# Ringo3-Eagle6.net
KiCad netlist of a schematic drawn in EAGLE
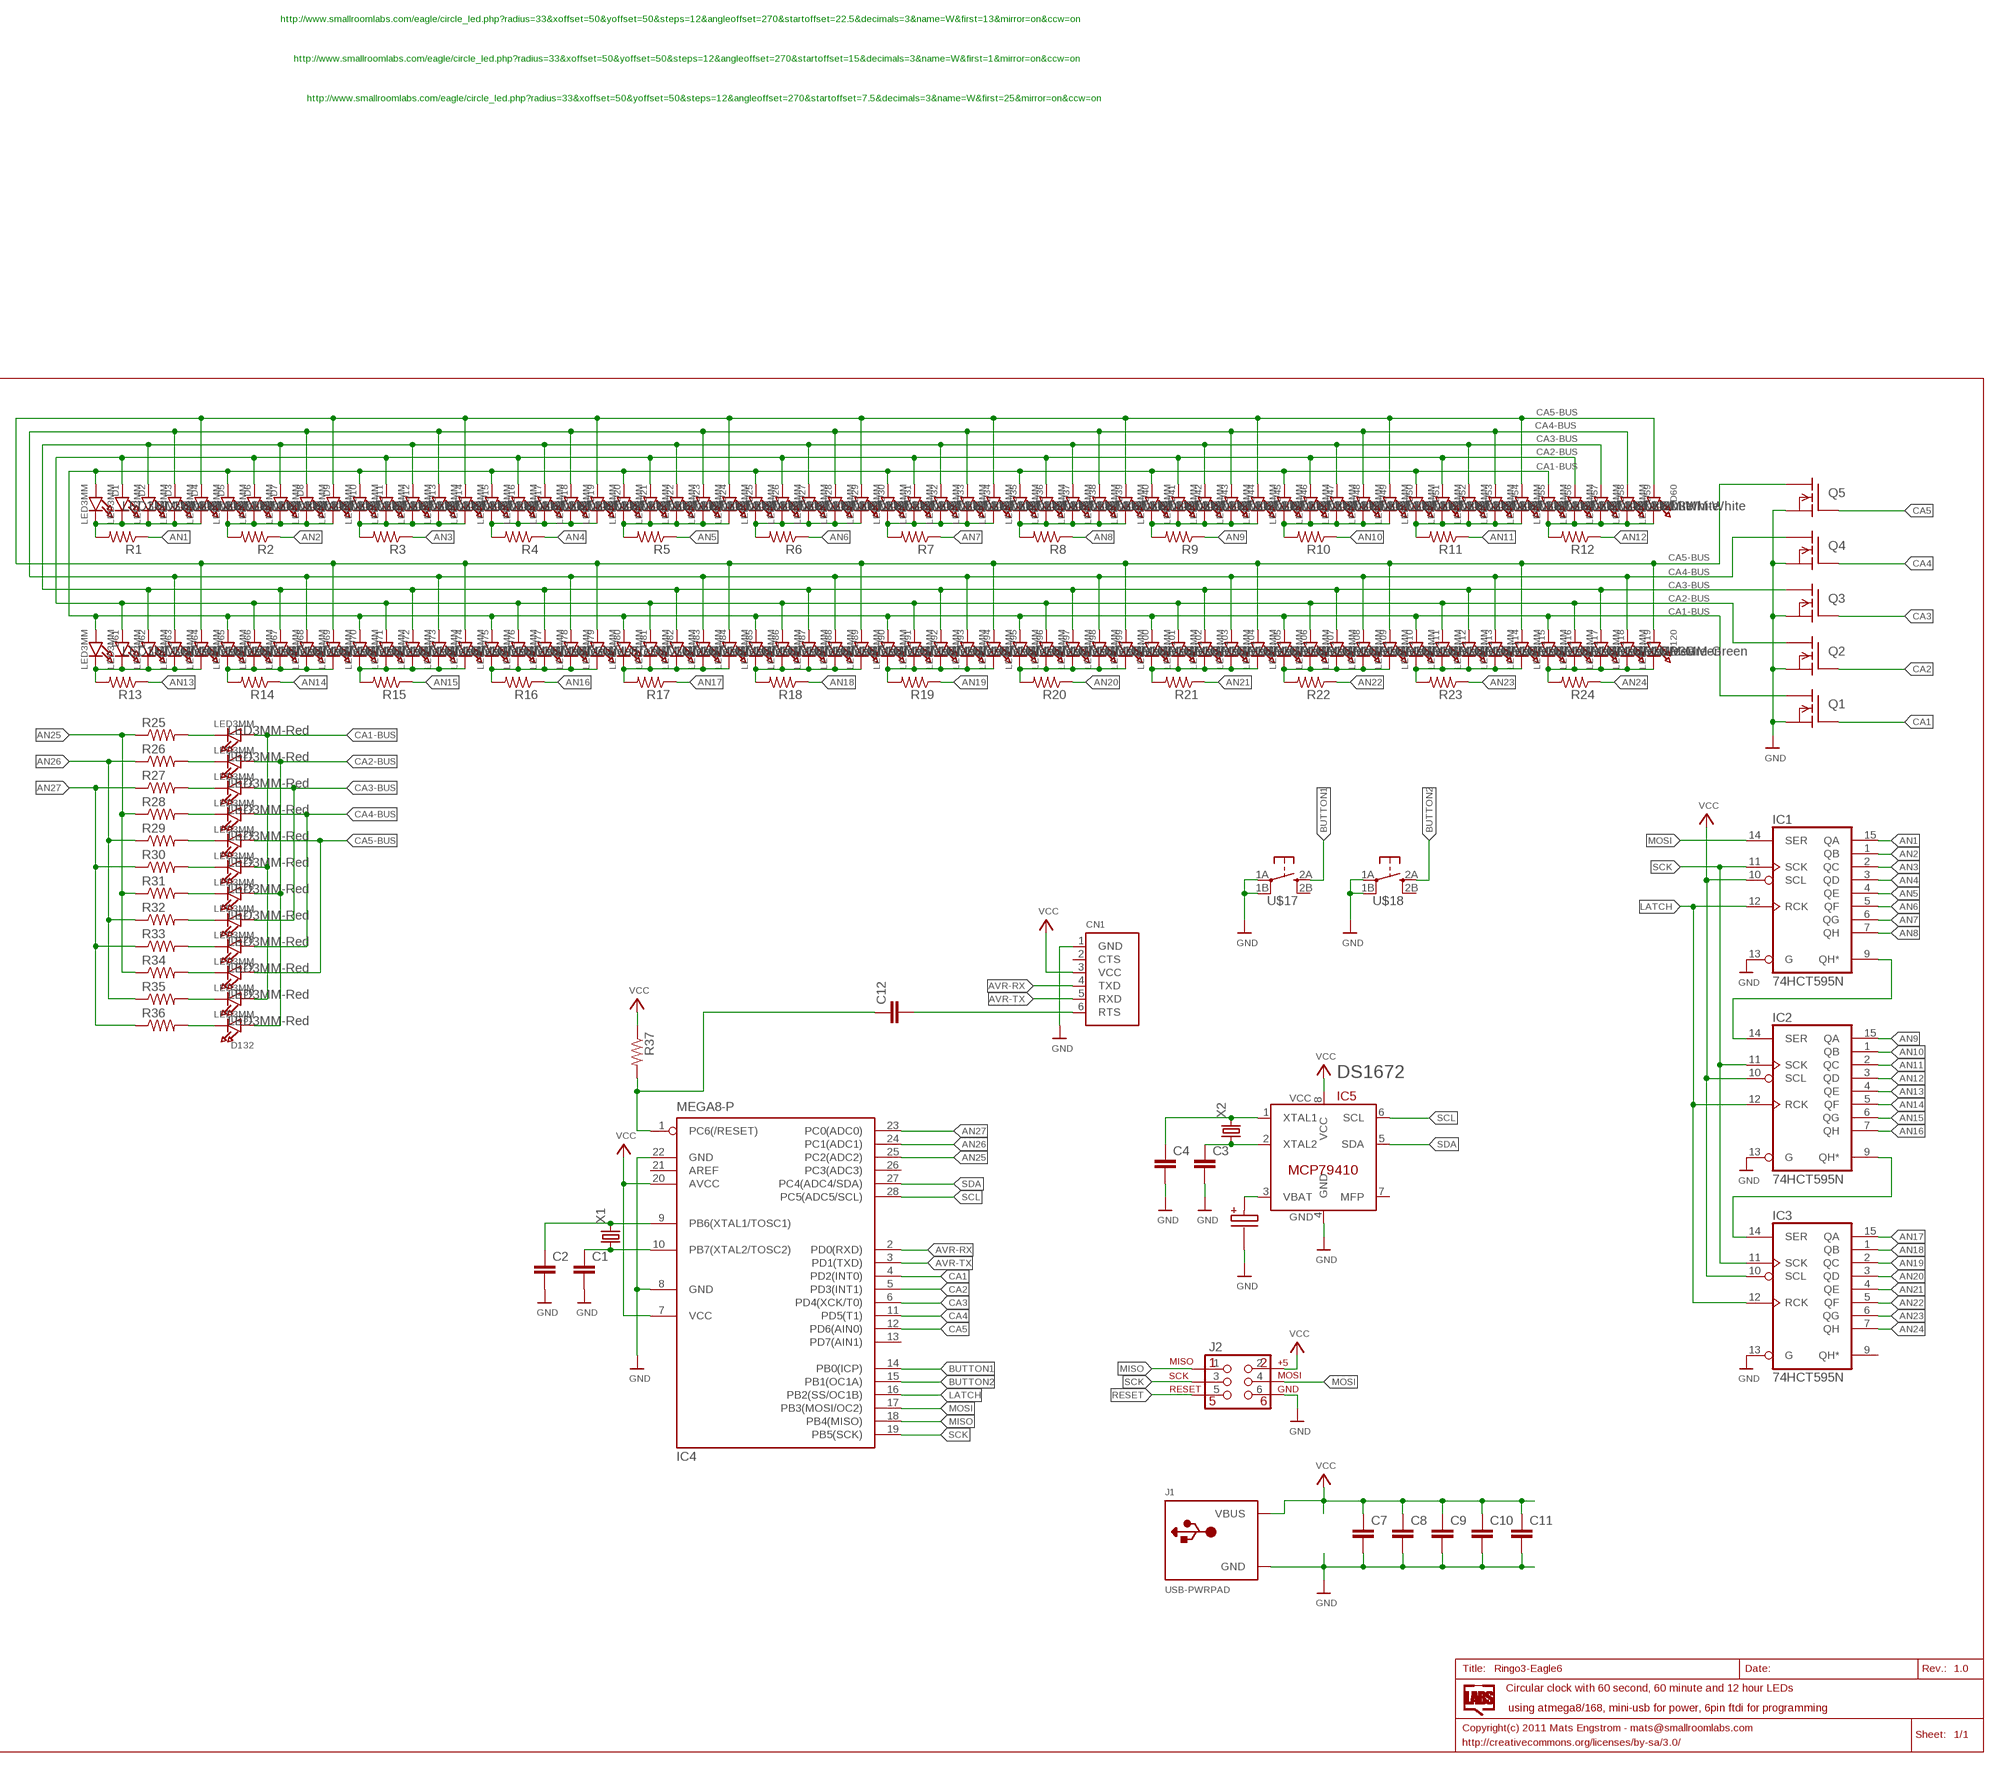
[diagram p0: schematic, sheet 1, part 1 of 2]
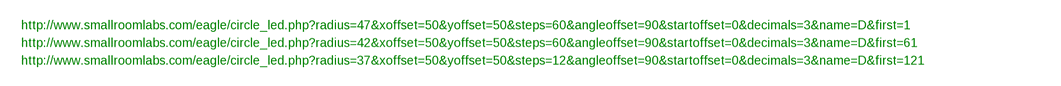
[diagram p1: schematic, sheet 1, part 2 of 2]

(export (version "E")
  (design (tool "Eeschema 10.0.6"))
  (components
    (comp (ref "C1")
      (value "CAPPTH")
      (footprint "eagle-import:CAP-PTH-SMALL")
      (libsource (lib "eagle-import") (part "CAPPTH"))
    )
    (comp (ref "C2")
      (value "CAPPTH")
      (footprint "eagle-import:CAP-PTH-SMALL")
      (libsource (lib "eagle-import") (part "CAPPTH"))
    )
    (comp (ref "C3")
      (value "CAPPTH")
      (footprint "eagle-import:CAP-PTH-SMALL")
      (libsource (lib "eagle-import") (part "CAPPTH"))
    )
    (comp (ref "C4")
      (value "CAPPTH")
      (footprint "eagle-import:CAP-PTH-SMALL")
      (libsource (lib "eagle-import") (part "CAPPTH"))
    )
    (comp (ref "C5")
      (value "CAPPOLSUPER13/5")
      (footprint "eagle-import:CAP-SUPER13_5")
      (libsource (lib "eagle-import") (part "CAPPOLSUPER13/5"))
    )
    (comp (ref "C7")
      (value "CAPPTH")
      (footprint "eagle-import:CAP-PTH-SMALL")
      (libsource (lib "eagle-import") (part "CAPPTH"))
    )
    (comp (ref "C8")
      (value "CAPPTH")
      (footprint "eagle-import:CAP-PTH-SMALL")
      (libsource (lib "eagle-import") (part "CAPPTH"))
    )
    (comp (ref "C9")
      (value "CAPPTH")
      (footprint "eagle-import:CAP-PTH-SMALL")
      (libsource (lib "eagle-import") (part "CAPPTH"))
    )
    (comp (ref "C10")
      (value "CAPPTH")
      (footprint "eagle-import:CAP-PTH-SMALL")
      (libsource (lib "eagle-import") (part "CAPPTH"))
    )
    (comp (ref "C11")
      (value "CAPPTH")
      (footprint "eagle-import:CAP-PTH-SMALL")
      (libsource (lib "eagle-import") (part "CAPPTH"))
    )
    (comp (ref "C12")
      (value "CAPPTH")
      (footprint "eagle-import:CAP-PTH-SMALL")
      (libsource (lib "eagle-import") (part "CAPPTH"))
    )
    (comp (ref "CN1")
      (value "FTDIUSBCABLE")
      (footprint "eagle-import:1X06_ROUND")
      (libsource (lib "eagle-import") (part "FTDIUSBCABLE"))
    )
    (comp (ref "D1")
      (value "LED3MM")
      (footprint "eagle-import:LED3MM")
      (libsource (lib "eagle-import") (part "LED3MM"))
    )
    (comp (ref "D2")
      (value "LED3MM")
      (footprint "eagle-import:LED3MM")
      (fields (field (name "EAGLEUP") "LED3MM-White"))
      (libsource (lib "eagle-import") (part "LED3MM"))
    )
    (comp (ref "D3")
      (value "LED3MM")
      (footprint "eagle-import:LED3MM")
      (fields (field (name "EAGLEUP") "LED3MM-White"))
      (libsource (lib "eagle-import") (part "LED3MM"))
    )
    (comp (ref "D4")
      (value "LED3MM")
      (footprint "eagle-import:LED3MM")
      (fields (field (name "EAGLEUP") "LED3MM-White"))
      (libsource (lib "eagle-import") (part "LED3MM"))
    )
    (comp (ref "D5")
      (value "LED3MM")
      (footprint "eagle-import:LED3MM")
      (fields (field (name "EAGLEUP") "LED3MM-White"))
      (libsource (lib "eagle-import") (part "LED3MM"))
    )
    (comp (ref "D6")
      (value "LED3MM")
      (footprint "eagle-import:LED3MM")
      (fields (field (name "EAGLEUP") "LED3MM-White"))
      (libsource (lib "eagle-import") (part "LED3MM"))
    )
    (comp (ref "D7")
      (value "LED3MM")
      (footprint "eagle-import:LED3MM")
      (fields (field (name "EAGLEUP") "LED3MM-White"))
      (libsource (lib "eagle-import") (part "LED3MM"))
    )
    (comp (ref "D8")
      (value "LED3MM")
      (footprint "eagle-import:LED3MM")
      (fields (field (name "EAGLEUP") "LED3MM-White"))
      (libsource (lib "eagle-import") (part "LED3MM"))
    )
    (comp (ref "D9")
      (value "LED3MM")
      (footprint "eagle-import:LED3MM")
      (fields (field (name "EAGLEUP") "LED3MM-White"))
      (libsource (lib "eagle-import") (part "LED3MM"))
    )
    (comp (ref "D10")
      (value "LED3MM")
      (footprint "eagle-import:LED3MM")
      (fields (field (name "EAGLEUP") "LED3MM-White"))
      (libsource (lib "eagle-import") (part "LED3MM"))
    )
    (comp (ref "D11")
      (value "LED3MM")
      (footprint "eagle-import:LED3MM")
      (fields (field (name "EAGLEUP") "LED3MM-White"))
      (libsource (lib "eagle-import") (part "LED3MM"))
    )
    (comp (ref "D12")
      (value "LED3MM")
      (footprint "eagle-import:LED3MM")
      (fields (field (name "EAGLEUP") "LED3MM-White"))
      (libsource (lib "eagle-import") (part "LED3MM"))
    )
    (comp (ref "D13")
      (value "LED3MM")
      (footprint "eagle-import:LED3MM")
      (fields (field (name "EAGLEUP") "LED3MM-White"))
      (libsource (lib "eagle-import") (part "LED3MM"))
    )
    (comp (ref "D14")
      (value "LED3MM")
      (footprint "eagle-import:LED3MM")
      (fields (field (name "EAGLEUP") "LED3MM-White"))
      (libsource (lib "eagle-import") (part "LED3MM"))
    )
    (comp (ref "D15")
      (value "LED3MM")
      (footprint "eagle-import:LED3MM")
      (fields (field (name "EAGLEUP") "LED3MM-White"))
      (libsource (lib "eagle-import") (part "LED3MM"))
    )
    (comp (ref "D16")
      (value "LED3MM")
      (footprint "eagle-import:LED3MM")
      (fields (field (name "EAGLEUP") "LED3MM-White"))
      (libsource (lib "eagle-import") (part "LED3MM"))
    )
    (comp (ref "D17")
      (value "LED3MM")
      (footprint "eagle-import:LED3MM")
      (fields (field (name "EAGLEUP") "LED3MM-White"))
      (libsource (lib "eagle-import") (part "LED3MM"))
    )
    (comp (ref "D18")
      (value "LED3MM")
      (footprint "eagle-import:LED3MM")
      (fields (field (name "EAGLEUP") "LED3MM-White"))
      (libsource (lib "eagle-import") (part "LED3MM"))
    )
    (comp (ref "D19")
      (value "LED3MM")
      (footprint "eagle-import:LED3MM")
      (fields (field (name "EAGLEUP") "LED3MM-White"))
      (libsource (lib "eagle-import") (part "LED3MM"))
    )
    (comp (ref "D20")
      (value "LED3MM")
      (footprint "eagle-import:LED3MM")
      (fields (field (name "EAGLEUP") "LED3MM-White"))
      (libsource (lib "eagle-import") (part "LED3MM"))
    )
    (comp (ref "D21")
      (value "LED3MM")
      (footprint "eagle-import:LED3MM")
      (fields (field (name "EAGLEUP") "LED3MM-White"))
      (libsource (lib "eagle-import") (part "LED3MM"))
    )
    (comp (ref "D22")
      (value "LED3MM")
      (footprint "eagle-import:LED3MM")
      (fields (field (name "EAGLEUP") "LED3MM-White"))
      (libsource (lib "eagle-import") (part "LED3MM"))
    )
    (comp (ref "D23")
      (value "LED3MM")
      (footprint "eagle-import:LED3MM")
      (fields (field (name "EAGLEUP") "LED3MM-White"))
      (libsource (lib "eagle-import") (part "LED3MM"))
    )
    (comp (ref "D24")
      (value "LED3MM")
      (footprint "eagle-import:LED3MM")
      (fields (field (name "EAGLEUP") "LED3MM-White"))
      (libsource (lib "eagle-import") (part "LED3MM"))
    )
    (comp (ref "D25")
      (value "LED3MM")
      (footprint "eagle-import:LED3MM")
      (fields (field (name "EAGLEUP") "LED3MM-White"))
      (libsource (lib "eagle-import") (part "LED3MM"))
    )
    (comp (ref "D26")
      (value "LED3MM")
      (footprint "eagle-import:LED3MM")
      (fields (field (name "EAGLEUP") "LED3MM-White"))
      (libsource (lib "eagle-import") (part "LED3MM"))
    )
    (comp (ref "D27")
      (value "LED3MM")
      (footprint "eagle-import:LED3MM")
      (fields (field (name "EAGLEUP") "LED3MM-White"))
      (libsource (lib "eagle-import") (part "LED3MM"))
    )
    (comp (ref "D28")
      (value "LED3MM")
      (footprint "eagle-import:LED3MM")
      (fields (field (name "EAGLEUP") "LED3MM-White"))
      (libsource (lib "eagle-import") (part "LED3MM"))
    )
    (comp (ref "D29")
      (value "LED3MM")
      (footprint "eagle-import:LED3MM")
      (fields (field (name "EAGLEUP") "LED3MM-White"))
      (libsource (lib "eagle-import") (part "LED3MM"))
    )
    (comp (ref "D30")
      (value "LED3MM")
      (footprint "eagle-import:LED3MM")
      (fields (field (name "EAGLEUP") "LED3MM-White"))
      (libsource (lib "eagle-import") (part "LED3MM"))
    )
    (comp (ref "D31")
      (value "LED3MM")
      (footprint "eagle-import:LED3MM")
      (fields (field (name "EAGLEUP") "LED3MM-White"))
      (libsource (lib "eagle-import") (part "LED3MM"))
    )
    (comp (ref "D32")
      (value "LED3MM")
      (footprint "eagle-import:LED3MM")
      (fields (field (name "EAGLEUP") "LED3MM-White"))
      (libsource (lib "eagle-import") (part "LED3MM"))
    )
    (comp (ref "D33")
      (value "LED3MM")
      (footprint "eagle-import:LED3MM")
      (fields (field (name "EAGLEUP") "LED3MM-White"))
      (libsource (lib "eagle-import") (part "LED3MM"))
    )
    (comp (ref "D34")
      (value "LED3MM")
      (footprint "eagle-import:LED3MM")
      (fields (field (name "EAGLEUP") "LED3MM-White"))
      (libsource (lib "eagle-import") (part "LED3MM"))
    )
    (comp (ref "D35")
      (value "LED3MM")
      (footprint "eagle-import:LED3MM")
      (fields (field (name "EAGLEUP") "LED3MM-White"))
      (libsource (lib "eagle-import") (part "LED3MM"))
    )
    (comp (ref "D36")
      (value "LED3MM")
      (footprint "eagle-import:LED3MM")
      (fields (field (name "EAGLEUP") "LED3MM-White"))
      (libsource (lib "eagle-import") (part "LED3MM"))
    )
    (comp (ref "D37")
      (value "LED3MM")
      (footprint "eagle-import:LED3MM")
      (fields (field (name "EAGLEUP") "LED3MM-White"))
      (libsource (lib "eagle-import") (part "LED3MM"))
    )
    (comp (ref "D38")
      (value "LED3MM")
      (footprint "eagle-import:LED3MM")
      (fields (field (name "EAGLEUP") "LED3MM-White"))
      (libsource (lib "eagle-import") (part "LED3MM"))
    )
    (comp (ref "D39")
      (value "LED3MM")
      (footprint "eagle-import:LED3MM")
      (fields (field (name "EAGLEUP") "LED3MM-White"))
      (libsource (lib "eagle-import") (part "LED3MM"))
    )
    (comp (ref "D40")
      (value "LED3MM")
      (footprint "eagle-import:LED3MM")
      (fields (field (name "EAGLEUP") "LED3MM-White"))
      (libsource (lib "eagle-import") (part "LED3MM"))
    )
    (comp (ref "D41")
      (value "LED3MM")
      (footprint "eagle-import:LED3MM")
      (fields (field (name "EAGLEUP") "LED3MM-White"))
      (libsource (lib "eagle-import") (part "LED3MM"))
    )
    (comp (ref "D42")
      (value "LED3MM")
      (footprint "eagle-import:LED3MM")
      (fields (field (name "EAGLEUP") "LED3MM-White"))
      (libsource (lib "eagle-import") (part "LED3MM"))
    )
    (comp (ref "D43")
      (value "LED3MM")
      (footprint "eagle-import:LED3MM")
      (fields (field (name "EAGLEUP") "LED3MM-White"))
      (libsource (lib "eagle-import") (part "LED3MM"))
    )
    (comp (ref "D44")
      (value "LED3MM")
      (footprint "eagle-import:LED3MM")
      (fields (field (name "EAGLEUP") "LED3MM-White"))
      (libsource (lib "eagle-import") (part "LED3MM"))
    )
    (comp (ref "D45")
      (value "LED3MM")
      (footprint "eagle-import:LED3MM")
      (fields (field (name "EAGLEUP") "LED3MM-White"))
      (libsource (lib "eagle-import") (part "LED3MM"))
    )
    (comp (ref "D46")
      (value "LED3MM")
      (footprint "eagle-import:LED3MM")
      (fields (field (name "EAGLEUP") "LED3MM-White"))
      (libsource (lib "eagle-import") (part "LED3MM"))
    )
    (comp (ref "D47")
      (value "LED3MM")
      (footprint "eagle-import:LED3MM")
      (fields (field (name "EAGLEUP") "LED3MM-White"))
      (libsource (lib "eagle-import") (part "LED3MM"))
    )
    (comp (ref "D48")
      (value "LED3MM")
      (footprint "eagle-import:LED3MM")
      (fields (field (name "EAGLEUP") "LED3MM-White"))
      (libsource (lib "eagle-import") (part "LED3MM"))
    )
    (comp (ref "D49")
      (value "LED3MM")
      (footprint "eagle-import:LED3MM")
      (fields (field (name "EAGLEUP") "LED3MM-White"))
      (libsource (lib "eagle-import") (part "LED3MM"))
    )
    (comp (ref "D50")
      (value "LED3MM")
      (footprint "eagle-import:LED3MM")
      (fields (field (name "EAGLEUP") "LED3MM-White"))
      (libsource (lib "eagle-import") (part "LED3MM"))
    )
    (comp (ref "D51")
      (value "LED3MM")
      (footprint "eagle-import:LED3MM")
      (fields (field (name "EAGLEUP") "LED3MM-White"))
      (libsource (lib "eagle-import") (part "LED3MM"))
    )
    (comp (ref "D52")
      (value "LED3MM")
      (footprint "eagle-import:LED3MM")
      (fields (field (name "EAGLEUP") "LED3MM-White"))
      (libsource (lib "eagle-import") (part "LED3MM"))
    )
    (comp (ref "D53")
      (value "LED3MM")
      (footprint "eagle-import:LED3MM")
      (fields (field (name "EAGLEUP") "LED3MM-White"))
      (libsource (lib "eagle-import") (part "LED3MM"))
    )
    (comp (ref "D54")
      (value "LED3MM")
      (footprint "eagle-import:LED3MM")
      (fields (field (name "EAGLEUP") "LED3MM-White"))
      (libsource (lib "eagle-import") (part "LED3MM"))
    )
    (comp (ref "D55")
      (value "LED3MM")
      (footprint "eagle-import:LED3MM")
      (fields (field (name "EAGLEUP") "LED3MM-White"))
      (libsource (lib "eagle-import") (part "LED3MM"))
    )
    (comp (ref "D56")
      (value "LED3MM")
      (footprint "eagle-import:LED3MM")
      (fields (field (name "EAGLEUP") "LED3MM-White"))
      (libsource (lib "eagle-import") (part "LED3MM"))
    )
    (comp (ref "D57")
      (value "LED3MM")
      (footprint "eagle-import:LED3MM")
      (fields (field (name "EAGLEUP") "LED3MM-White"))
      (libsource (lib "eagle-import") (part "LED3MM"))
    )
    (comp (ref "D58")
      (value "LED3MM")
      (footprint "eagle-import:LED3MM")
      (fields (field (name "EAGLEUP") "LED3MM-White"))
      (libsource (lib "eagle-import") (part "LED3MM"))
    )
    (comp (ref "D59")
      (value "LED3MM")
      (footprint "eagle-import:LED3MM")
      (fields (field (name "EAGLEUP") "LED3MM-White"))
      (libsource (lib "eagle-import") (part "LED3MM"))
    )
    (comp (ref "D60")
      (value "LED3MM")
      (footprint "eagle-import:LED3MM")
      (fields (field (name "EAGLEUP") "LED3MM-White"))
      (libsource (lib "eagle-import") (part "LED3MM"))
    )
    (comp (ref "D61")
      (value "LED3MM")
      (footprint "eagle-import:LED3MM")
      (libsource (lib "eagle-import") (part "LED3MM"))
    )
    (comp (ref "D62")
      (value "LED3MM")
      (footprint "eagle-import:LED3MM")
      (fields (field (name "EAGLEUP") "LED3MM-Green"))
      (libsource (lib "eagle-import") (part "LED3MM"))
    )
    (comp (ref "D63")
      (value "LED3MM")
      (footprint "eagle-import:LED3MM")
      (fields (field (name "EAGLEUP") "LED3MM-Green"))
      (libsource (lib "eagle-import") (part "LED3MM"))
    )
    (comp (ref "D64")
      (value "LED3MM")
      (footprint "eagle-import:LED3MM")
      (fields (field (name "EAGLEUP") "LED3MM-Green"))
      (libsource (lib "eagle-import") (part "LED3MM"))
    )
    (comp (ref "D65")
      (value "LED3MM")
      (footprint "eagle-import:LED3MM")
      (fields (field (name "EAGLEUP") "LED3MM-Green"))
      (libsource (lib "eagle-import") (part "LED3MM"))
    )
    (comp (ref "D66")
      (value "LED3MM")
      (footprint "eagle-import:LED3MM")
      (fields (field (name "EAGLEUP") "LED3MM-Green"))
      (libsource (lib "eagle-import") (part "LED3MM"))
    )
    (comp (ref "D67")
      (value "LED3MM")
      (footprint "eagle-import:LED3MM")
      (fields (field (name "EAGLEUP") "LED3MM-Green"))
      (libsource (lib "eagle-import") (part "LED3MM"))
    )
    (comp (ref "D68")
      (value "LED3MM")
      (footprint "eagle-import:LED3MM")
      (fields (field (name "EAGLEUP") "LED3MM-Green"))
      (libsource (lib "eagle-import") (part "LED3MM"))
    )
    (comp (ref "D69")
      (value "LED3MM")
      (footprint "eagle-import:LED3MM")
      (fields (field (name "EAGLEUP") "LED3MM-Green"))
      (libsource (lib "eagle-import") (part "LED3MM"))
    )
    (comp (ref "D70")
      (value "LED3MM")
      (footprint "eagle-import:LED3MM")
      (fields (field (name "EAGLEUP") "LED3MM-Green"))
      (libsource (lib "eagle-import") (part "LED3MM"))
    )
    (comp (ref "D71")
      (value "LED3MM")
      (footprint "eagle-import:LED3MM")
      (fields (field (name "EAGLEUP") "LED3MM-Green"))
      (libsource (lib "eagle-import") (part "LED3MM"))
    )
    (comp (ref "D72")
      (value "LED3MM")
      (footprint "eagle-import:LED3MM")
      (fields (field (name "EAGLEUP") "LED3MM-Green"))
      (libsource (lib "eagle-import") (part "LED3MM"))
    )
    (comp (ref "D73")
      (value "LED3MM")
      (footprint "eagle-import:LED3MM")
      (fields (field (name "EAGLEUP") "LED3MM-Green"))
      (libsource (lib "eagle-import") (part "LED3MM"))
    )
    (comp (ref "D74")
      (value "LED3MM")
      (footprint "eagle-import:LED3MM")
      (fields (field (name "EAGLEUP") "LED3MM-Green"))
      (libsource (lib "eagle-import") (part "LED3MM"))
    )
    (comp (ref "D75")
      (value "LED3MM")
      (footprint "eagle-import:LED3MM")
      (fields (field (name "EAGLEUP") "LED3MM-Green"))
      (libsource (lib "eagle-import") (part "LED3MM"))
    )
    (comp (ref "D76")
      (value "LED3MM")
      (footprint "eagle-import:LED3MM")
      (fields (field (name "EAGLEUP") "LED3MM-Green"))
      (libsource (lib "eagle-import") (part "LED3MM"))
    )
    (comp (ref "D77")
      (value "LED3MM")
      (footprint "eagle-import:LED3MM")
      (fields (field (name "EAGLEUP") "LED3MM-Green"))
      (libsource (lib "eagle-import") (part "LED3MM"))
    )
    (comp (ref "D78")
      (value "LED3MM")
      (footprint "eagle-import:LED3MM")
      (fields (field (name "EAGLEUP") "LED3MM-Green"))
      (libsource (lib "eagle-import") (part "LED3MM"))
    )
    (comp (ref "D79")
      (value "LED3MM")
      (footprint "eagle-import:LED3MM")
      (fields (field (name "EAGLEUP") "LED3MM-Green"))
      (libsource (lib "eagle-import") (part "LED3MM"))
    )
    (comp (ref "D80")
      (value "LED3MM")
      (footprint "eagle-import:LED3MM")
      (libsource (lib "eagle-import") (part "LED3MM"))
    )
    (comp (ref "D81")
      (value "LED3MM")
      (footprint "eagle-import:LED3MM")
      (fields (field (name "EAGLEUP") "LED3MM-Green"))
      (libsource (lib "eagle-import") (part "LED3MM"))
    )
    (comp (ref "D82")
      (value "LED3MM")
      (footprint "eagle-import:LED3MM")
      (fields (field (name "EAGLEUP") "LED3MM-Green"))
      (libsource (lib "eagle-import") (part "LED3MM"))
    )
    (comp (ref "D83")
      (value "LED3MM")
      (footprint "eagle-import:LED3MM")
      (fields (field (name "EAGLEUP") "LED3MM-Green"))
      (libsource (lib "eagle-import") (part "LED3MM"))
    )
    (comp (ref "D84")
      (value "LED3MM")
      (footprint "eagle-import:LED3MM")
      (fields (field (name "EAGLEUP") "LED3MM-Green"))
      (libsource (lib "eagle-import") (part "LED3MM"))
    )
    (comp (ref "D85")
      (value "LED3MM")
      (footprint "eagle-import:LED3MM")
      (fields (field (name "EAGLEUP") "LED3MM-Green"))
      (libsource (lib "eagle-import") (part "LED3MM"))
    )
    (comp (ref "D86")
      (value "LED3MM")
      (footprint "eagle-import:LED3MM")
      (fields (field (name "EAGLEUP") "LED3MM-Green"))
      (libsource (lib "eagle-import") (part "LED3MM"))
    )
    (comp (ref "D87")
      (value "LED3MM")
      (footprint "eagle-import:LED3MM")
      (fields (field (name "EAGLEUP") "LED3MM-Green"))
      (libsource (lib "eagle-import") (part "LED3MM"))
    )
    (comp (ref "D88")
      (value "LED3MM")
      (footprint "eagle-import:LED3MM")
      (fields (field (name "EAGLEUP") "LED3MM-Green"))
      (libsource (lib "eagle-import") (part "LED3MM"))
    )
    (comp (ref "D89")
      (value "LED3MM")
      (footprint "eagle-import:LED3MM")
      (fields (field (name "EAGLEUP") "LED3MM-Green"))
      (libsource (lib "eagle-import") (part "LED3MM"))
    )
    (comp (ref "D90")
      (value "LED3MM")
      (footprint "eagle-import:LED3MM")
      (fields (field (name "EAGLEUP") "LED3MM-Green"))
      (libsource (lib "eagle-import") (part "LED3MM"))
    )
    (comp (ref "D91")
      (value "LED3MM")
      (footprint "eagle-import:LED3MM")
      (fields (field (name "EAGLEUP") "LED3MM-Green"))
      (libsource (lib "eagle-import") (part "LED3MM"))
    )
    (comp (ref "D92")
      (value "LED3MM")
      (footprint "eagle-import:LED3MM")
      (fields (field (name "EAGLEUP") "LED3MM-Green"))
      (libsource (lib "eagle-import") (part "LED3MM"))
    )
    (comp (ref "D93")
      (value "LED3MM")
      (footprint "eagle-import:LED3MM")
      (fields (field (name "EAGLEUP") "LED3MM-Green"))
      (libsource (lib "eagle-import") (part "LED3MM"))
    )
    (comp (ref "D94")
      (value "LED3MM")
      (footprint "eagle-import:LED3MM")
      (fields (field (name "EAGLEUP") "LED3MM-Green"))
      (libsource (lib "eagle-import") (part "LED3MM"))
    )
    (comp (ref "D95")
      (value "LED3MM")
      (footprint "eagle-import:LED3MM")
      (fields (field (name "EAGLEUP") "LED3MM-Green"))
      (libsource (lib "eagle-import") (part "LED3MM"))
    )
    (comp (ref "D96")
      (value "LED3MM")
      (footprint "eagle-import:LED3MM")
      (fields (field (name "EAGLEUP") "LED3MM-Green"))
      (libsource (lib "eagle-import") (part "LED3MM"))
    )
    (comp (ref "D97")
      (value "LED3MM")
      (footprint "eagle-import:LED3MM")
      (fields (field (name "EAGLEUP") "LED3MM-Green"))
      (libsource (lib "eagle-import") (part "LED3MM"))
    )
    (comp (ref "D98")
      (value "LED3MM")
      (footprint "eagle-import:LED3MM")
      (fields (field (name "EAGLEUP") "LED3MM-Green"))
      (libsource (lib "eagle-import") (part "LED3MM"))
    )
    (comp (ref "D99")
      (value "LED3MM")
      (footprint "eagle-import:LED3MM")
      (fields (field (name "EAGLEUP") "LED3MM-Green"))
      (libsource (lib "eagle-import") (part "LED3MM"))
    )
    (comp (ref "D100")
      (value "LED3MM")
      (footprint "eagle-import:LED3MM")
      (fields (field (name "EAGLEUP") "LED3MM-Green"))
      (libsource (lib "eagle-import") (part "LED3MM"))
    )
    (comp (ref "D101")
      (value "LED3MM")
      (footprint "eagle-import:LED3MM")
      (fields (field (name "EAGLEUP") "LED3MM-Green"))
      (libsource (lib "eagle-import") (part "LED3MM"))
    )
    (comp (ref "D102")
      (value "LED3MM")
      (footprint "eagle-import:LED3MM")
      (fields (field (name "EAGLEUP") "LED3MM-Green"))
      (libsource (lib "eagle-import") (part "LED3MM"))
    )
    (comp (ref "D103")
      (value "LED3MM")
      (footprint "eagle-import:LED3MM")
      (fields (field (name "EAGLEUP") "LED3MM-Green"))
      (libsource (lib "eagle-import") (part "LED3MM"))
    )
    (comp (ref "D104")
      (value "LED3MM")
      (footprint "eagle-import:LED3MM")
      (fields (field (name "EAGLEUP") "LED3MM-Green"))
      (libsource (lib "eagle-import") (part "LED3MM"))
    )
    (comp (ref "D105")
      (value "LED3MM")
      (footprint "eagle-import:LED3MM")
      (fields (field (name "EAGLEUP") "LED3MM-Green"))
      (libsource (lib "eagle-import") (part "LED3MM"))
    )
    (comp (ref "D106")
      (value "LED3MM")
      (footprint "eagle-import:LED3MM")
      (fields (field (name "EAGLEUP") "LED3MM-Green"))
      (libsource (lib "eagle-import") (part "LED3MM"))
    )
    (comp (ref "D107")
      (value "LED3MM")
      (footprint "eagle-import:LED3MM")
      (fields (field (name "EAGLEUP") "LED3MM-Green"))
      (libsource (lib "eagle-import") (part "LED3MM"))
    )
    (comp (ref "D108")
      (value "LED3MM")
      (footprint "eagle-import:LED3MM")
      (fields (field (name "EAGLEUP") "LED3MM-Green"))
      (libsource (lib "eagle-import") (part "LED3MM"))
    )
    (comp (ref "D109")
      (value "LED3MM")
      (footprint "eagle-import:LED3MM")
      (fields (field (name "EAGLEUP") "LED3MM-Green"))
      (libsource (lib "eagle-import") (part "LED3MM"))
    )
    (comp (ref "D110")
      (value "LED3MM")
      (footprint "eagle-import:LED3MM")
      (fields (field (name "EAGLEUP") "LED3MM-Green"))
      (libsource (lib "eagle-import") (part "LED3MM"))
    )
    (comp (ref "D111")
      (value "LED3MM")
      (footprint "eagle-import:LED3MM")
      (fields (field (name "EAGLEUP") "LED3MM-Green"))
      (libsource (lib "eagle-import") (part "LED3MM"))
    )
    (comp (ref "D112")
      (value "LED3MM")
      (footprint "eagle-import:LED3MM")
      (fields (field (name "EAGLEUP") "LED3MM-Green"))
      (libsource (lib "eagle-import") (part "LED3MM"))
    )
    (comp (ref "D113")
      (value "LED3MM")
      (footprint "eagle-import:LED3MM")
      (fields (field (name "EAGLEUP") "LED3MM-Green"))
      (libsource (lib "eagle-import") (part "LED3MM"))
    )
    (comp (ref "D114")
      (value "LED3MM")
      (footprint "eagle-import:LED3MM")
      (fields (field (name "EAGLEUP") "LED3MM-Green"))
      (libsource (lib "eagle-import") (part "LED3MM"))
    )
    (comp (ref "D115")
      (value "LED3MM")
      (footprint "eagle-import:LED3MM")
      (fields (field (name "EAGLEUP") "LED3MM-Green"))
      (libsource (lib "eagle-import") (part "LED3MM"))
    )
    (comp (ref "D116")
      (value "LED3MM")
      (footprint "eagle-import:LED3MM")
      (fields (field (name "EAGLEUP") "LED3MM-Green"))
      (libsource (lib "eagle-import") (part "LED3MM"))
    )
    (comp (ref "D117")
      (value "LED3MM")
      (footprint "eagle-import:LED3MM")
      (fields (field (name "EAGLEUP") "LED3MM-Green"))
      (libsource (lib "eagle-import") (part "LED3MM"))
    )
    (comp (ref "D118")
      (value "LED3MM")
      (footprint "eagle-import:LED3MM")
      (fields (field (name "EAGLEUP") "LED3MM-Green"))
      (libsource (lib "eagle-import") (part "LED3MM"))
    )
    (comp (ref "D119")
      (value "LED3MM")
      (footprint "eagle-import:LED3MM")
      (fields (field (name "EAGLEUP") "LED3MM-Green"))
      (libsource (lib "eagle-import") (part "LED3MM"))
    )
    (comp (ref "D120")
      (value "LED3MM")
      (footprint "eagle-import:LED3MM")
      (fields (field (name "EAGLEUP") "LED3MM-Green"))
      (libsource (lib "eagle-import") (part "LED3MM"))
    )
    (comp (ref "D121")
      (value "LED3MM")
      (footprint "eagle-import:LED3MM")
      (fields (field (name "EAGLEUP") "LED3MM-Red"))
      (libsource (lib "eagle-import") (part "LED3MM"))
    )
    (comp (ref "D122")
      (value "LED3MM")
      (footprint "eagle-import:LED3MM")
      (fields (field (name "EAGLEUP") "LED3MM-Red"))
      (libsource (lib "eagle-import") (part "LED3MM"))
    )
    (comp (ref "D123")
      (value "LED3MM")
      (footprint "eagle-import:LED3MM")
      (fields (field (name "EAGLEUP") "LED3MM-Red"))
      (libsource (lib "eagle-import") (part "LED3MM"))
    )
    (comp (ref "D124")
      (value "LED3MM")
      (footprint "eagle-import:LED3MM")
      (fields (field (name "EAGLEUP") "LED3MM-Red"))
      (libsource (lib "eagle-import") (part "LED3MM"))
    )
    (comp (ref "D125")
      (value "LED3MM")
      (footprint "eagle-import:LED3MM")
      (fields (field (name "EAGLEUP") "LED3MM-Red"))
      (libsource (lib "eagle-import") (part "LED3MM"))
    )
    (comp (ref "D126")
      (value "LED3MM")
      (footprint "eagle-import:LED3MM")
      (fields (field (name "EAGLEUP") "LED3MM-Red"))
      (libsource (lib "eagle-import") (part "LED3MM"))
    )
    (comp (ref "D127")
      (value "LED3MM")
      (footprint "eagle-import:LED3MM")
      (fields (field (name "EAGLEUP") "LED3MM-Red"))
      (libsource (lib "eagle-import") (part "LED3MM"))
    )
    (comp (ref "D128")
      (value "LED3MM")
      (footprint "eagle-import:LED3MM")
      (fields (field (name "EAGLEUP") "LED3MM-Red"))
      (libsource (lib "eagle-import") (part "LED3MM"))
    )
    (comp (ref "D129")
      (value "LED3MM")
      (footprint "eagle-import:LED3MM")
      (fields (field (name "EAGLEUP") "LED3MM-Red"))
      (libsource (lib "eagle-import") (part "LED3MM"))
    )
    (comp (ref "D130")
      (value "LED3MM")
      (footprint "eagle-import:LED3MM")
      (fields (field (name "EAGLEUP") "LED3MM-Red"))
      (libsource (lib "eagle-import") (part "LED3MM"))
    )
    (comp (ref "D131")
      (value "LED3MM")
      (footprint "eagle-import:LED3MM")
      (fields (field (name "EAGLEUP") "LED3MM-Red"))
      (libsource (lib "eagle-import") (part "LED3MM"))
    )
    (comp (ref "D132")
      (value "LED3MM")
      (footprint "eagle-import:LED3MM")
      (fields (field (name "EAGLEUP") "LED3MM-Red"))
      (libsource (lib "eagle-import") (part "LED3MM"))
    )
    (comp (ref "IC1")
      (value "74HCT595N")
      (footprint "eagle-import:DIL16")
      (libsource (lib "eagle-import") (part "74595NHCT"))
    )
    (comp (ref "IC2")
      (value "74HCT595N")
      (footprint "eagle-import:DIL16")
      (libsource (lib "eagle-import") (part "74595NHCT"))
    )
    (comp (ref "IC3")
      (value "74HCT595N")
      (footprint "eagle-import:DIL16")
      (libsource (lib "eagle-import") (part "74595NHCT"))
    )
    (comp (ref "IC4")
      (value "MEGA8-P")
      (footprint "eagle-import:DIL28-3")
      (libsource (lib "eagle-import") (part "MEGA8-P"))
    )
    (comp (ref "IC5")
      (value "MCP79410DIL")
      (footprint "eagle-import:DIL08-LONG")
      (libsource (lib "eagle-import") (part "MCP79410DIL"))
    )
    (comp (ref "J1")
      (value "USB-PWRPAD")
      (footprint "eagle-import:USB-MINIB-PTH-PWR-PAD")
      (libsource (lib "eagle-import") (part "USB-PWRPAD"))
    )
    (comp (ref "J2")
      (value "AVR-ISP6_TOUCH")
      (footprint "eagle-import:ISP-TOUCH")
      (libsource (lib "eagle-import") (part "AVR-ISP6_TOUCH"))
    )
    (comp (ref "Q1")
      (value "N-FETSTR")
      (footprint "eagle-import:TO92-STRAIGHT")
      (libsource (lib "eagle-import") (part "N-FETSTR"))
    )
    (comp (ref "Q2")
      (value "N-FETSTR")
      (footprint "eagle-import:TO92-STRAIGHT")
      (libsource (lib "eagle-import") (part "N-FETSTR"))
    )
    (comp (ref "Q3")
      (value "N-FETSTR")
      (footprint "eagle-import:TO92-STRAIGHT")
      (libsource (lib "eagle-import") (part "N-FETSTR"))
    )
    (comp (ref "Q4")
      (value "N-FETSTR")
      (footprint "eagle-import:TO92-STRAIGHT")
      (libsource (lib "eagle-import") (part "N-FETSTR"))
    )
    (comp (ref "Q5")
      (value "N-FETSTR")
      (footprint "eagle-import:TO92-STRAIGHT")
      (libsource (lib "eagle-import") (part "N-FETSTR"))
    )
    (comp (ref "R1")
      (value "RESISTORAXIAL-0.3")
      (footprint "eagle-import:AXIAL-0.3")
      (libsource (lib "eagle-import") (part "RESISTORAXIAL-0.3"))
    )
    (comp (ref "R2")
      (value "RESISTORAXIAL-0.3")
      (footprint "eagle-import:AXIAL-0.3")
      (libsource (lib "eagle-import") (part "RESISTORAXIAL-0.3"))
    )
    (comp (ref "R3")
      (value "RESISTORAXIAL-0.3")
      (footprint "eagle-import:AXIAL-0.3")
      (libsource (lib "eagle-import") (part "RESISTORAXIAL-0.3"))
    )
    (comp (ref "R4")
      (value "RESISTORAXIAL-0.3")
      (footprint "eagle-import:AXIAL-0.3")
      (libsource (lib "eagle-import") (part "RESISTORAXIAL-0.3"))
    )
    (comp (ref "R5")
      (value "RESISTORAXIAL-0.3")
      (footprint "eagle-import:AXIAL-0.3")
      (libsource (lib "eagle-import") (part "RESISTORAXIAL-0.3"))
    )
    (comp (ref "R6")
      (value "RESISTORAXIAL-0.3")
      (footprint "eagle-import:AXIAL-0.3")
      (libsource (lib "eagle-import") (part "RESISTORAXIAL-0.3"))
    )
    (comp (ref "R7")
      (value "RESISTORAXIAL-0.3")
      (footprint "eagle-import:AXIAL-0.3")
      (libsource (lib "eagle-import") (part "RESISTORAXIAL-0.3"))
    )
    (comp (ref "R8")
      (value "RESISTORAXIAL-0.3")
      (footprint "eagle-import:AXIAL-0.3")
      (libsource (lib "eagle-import") (part "RESISTORAXIAL-0.3"))
    )
    (comp (ref "R9")
      (value "RESISTORAXIAL-0.3")
      (footprint "eagle-import:AXIAL-0.3")
      (libsource (lib "eagle-import") (part "RESISTORAXIAL-0.3"))
    )
    (comp (ref "R10")
      (value "RESISTORAXIAL-0.3")
      (footprint "eagle-import:AXIAL-0.3")
      (libsource (lib "eagle-import") (part "RESISTORAXIAL-0.3"))
    )
    (comp (ref "R11")
      (value "RESISTORAXIAL-0.3")
      (footprint "eagle-import:AXIAL-0.3")
      (libsource (lib "eagle-import") (part "RESISTORAXIAL-0.3"))
    )
    (comp (ref "R12")
      (value "RESISTORAXIAL-0.3")
      (footprint "eagle-import:AXIAL-0.3")
      (libsource (lib "eagle-import") (part "RESISTORAXIAL-0.3"))
    )
    (comp (ref "R13")
      (value "RESISTORAXIAL-0.3")
      (footprint "eagle-import:AXIAL-0.3")
      (libsource (lib "eagle-import") (part "RESISTORAXIAL-0.3"))
    )
    (comp (ref "R14")
      (value "RESISTORAXIAL-0.3")
      (footprint "eagle-import:AXIAL-0.3")
      (libsource (lib "eagle-import") (part "RESISTORAXIAL-0.3"))
    )
    (comp (ref "R15")
      (value "RESISTORAXIAL-0.3")
      (footprint "eagle-import:AXIAL-0.3")
      (libsource (lib "eagle-import") (part "RESISTORAXIAL-0.3"))
    )
    (comp (ref "R16")
      (value "RESISTORAXIAL-0.3")
      (footprint "eagle-import:AXIAL-0.3")
      (libsource (lib "eagle-import") (part "RESISTORAXIAL-0.3"))
    )
    (comp (ref "R17")
      (value "RESISTORAXIAL-0.3")
      (footprint "eagle-import:AXIAL-0.3")
      (libsource (lib "eagle-import") (part "RESISTORAXIAL-0.3"))
    )
    (comp (ref "R18")
      (value "RESISTORAXIAL-0.3")
      (footprint "eagle-import:AXIAL-0.3")
      (libsource (lib "eagle-import") (part "RESISTORAXIAL-0.3"))
    )
    (comp (ref "R19")
      (value "RESISTORAXIAL-0.3")
      (footprint "eagle-import:AXIAL-0.3")
      (libsource (lib "eagle-import") (part "RESISTORAXIAL-0.3"))
    )
    (comp (ref "R20")
      (value "RESISTORAXIAL-0.3")
      (footprint "eagle-import:AXIAL-0.3")
      (libsource (lib "eagle-import") (part "RESISTORAXIAL-0.3"))
    )
    (comp (ref "R21")
      (value "RESISTORAXIAL-0.3")
      (footprint "eagle-import:AXIAL-0.3")
      (libsource (lib "eagle-import") (part "RESISTORAXIAL-0.3"))
    )
    (comp (ref "R22")
      (value "RESISTORAXIAL-0.3")
      (footprint "eagle-import:AXIAL-0.3")
      (libsource (lib "eagle-import") (part "RESISTORAXIAL-0.3"))
    )
    (comp (ref "R23")
      (value "RESISTORAXIAL-0.3")
      (footprint "eagle-import:AXIAL-0.3")
      (libsource (lib "eagle-import") (part "RESISTORAXIAL-0.3"))
    )
    (comp (ref "R24")
      (value "RESISTORAXIAL-0.3")
      (footprint "eagle-import:AXIAL-0.3")
      (libsource (lib "eagle-import") (part "RESISTORAXIAL-0.3"))
    )
    (comp (ref "R25")
      (value "RESISTORAXIAL-0.3")
      (footprint "eagle-import:AXIAL-0.3")
      (libsource (lib "eagle-import") (part "RESISTORAXIAL-0.3"))
    )
    (comp (ref "R26")
      (value "RESISTORAXIAL-0.3")
      (footprint "eagle-import:AXIAL-0.3")
      (libsource (lib "eagle-import") (part "RESISTORAXIAL-0.3"))
    )
    (comp (ref "R27")
      (value "RESISTORAXIAL-0.3")
      (footprint "eagle-import:AXIAL-0.3")
      (libsource (lib "eagle-import") (part "RESISTORAXIAL-0.3"))
    )
    (comp (ref "R28")
      (value "RESISTORAXIAL-0.3")
      (footprint "eagle-import:AXIAL-0.3")
      (libsource (lib "eagle-import") (part "RESISTORAXIAL-0.3"))
    )
    (comp (ref "R29")
      (value "RESISTORAXIAL-0.3")
      (footprint "eagle-import:AXIAL-0.3")
      (libsource (lib "eagle-import") (part "RESISTORAXIAL-0.3"))
    )
    (comp (ref "R30")
      (value "RESISTORAXIAL-0.3")
      (footprint "eagle-import:AXIAL-0.3")
      (libsource (lib "eagle-import") (part "RESISTORAXIAL-0.3"))
    )
    (comp (ref "R31")
      (value "RESISTORAXIAL-0.3")
      (footprint "eagle-import:AXIAL-0.3")
      (libsource (lib "eagle-import") (part "RESISTORAXIAL-0.3"))
    )
    (comp (ref "R32")
      (value "RESISTORAXIAL-0.3")
      (footprint "eagle-import:AXIAL-0.3")
      (libsource (lib "eagle-import") (part "RESISTORAXIAL-0.3"))
    )
    (comp (ref "R33")
      (value "RESISTORAXIAL-0.3")
      (footprint "eagle-import:AXIAL-0.3")
      (libsource (lib "eagle-import") (part "RESISTORAXIAL-0.3"))
    )
    (comp (ref "R34")
      (value "RESISTORAXIAL-0.3")
      (footprint "eagle-import:AXIAL-0.3")
      (libsource (lib "eagle-import") (part "RESISTORAXIAL-0.3"))
    )
    (comp (ref "R35")
      (value "RESISTORAXIAL-0.3")
      (footprint "eagle-import:AXIAL-0.3")
      (libsource (lib "eagle-import") (part "RESISTORAXIAL-0.3"))
    )
    (comp (ref "R36")
      (value "RESISTORAXIAL-0.3")
      (footprint "eagle-import:AXIAL-0.3")
      (libsource (lib "eagle-import") (part "RESISTORAXIAL-0.3"))
    )
    (comp (ref "R37")
      (value "RESISTORAXIAL-0.3")
      (footprint "eagle-import:AXIAL-0.3")
      (libsource (lib "eagle-import") (part "RESISTORAXIAL-0.3"))
    )
    (comp (ref "U$17")
      (value "TACTILETACT-4.5X4.5-PTH")
      (footprint "eagle-import:TACTILE-PTH-4.5X4.5")
      (libsource (lib "eagle-import") (part "TACTILETACT-4.5X4.5-PTH"))
    )
    (comp (ref "U$18")
      (value "TACTILETACT-4.5X4.5-PTH")
      (footprint "eagle-import:TACTILE-PTH-4.5X4.5")
      (libsource (lib "eagle-import") (part "TACTILETACT-4.5X4.5-PTH"))
    )
    (comp (ref "X1")
      (value "CRYSTALHC49US")
      (footprint "eagle-import:HC49US")
      (libsource (lib "eagle-import") (part "CRYSTALHC49US"))
    )
    (comp (ref "X2")
      (value "CRYSTALTC26H")
      (footprint "eagle-import:TC26H")
      (libsource (lib "eagle-import") (part "CRYSTALTC26H"))
    )
  )
  (nets
    (net (code "1") (name "AN1") (class "Default")
      (node (ref "IC1") (pin "15") (pinfunction "QA_15") (pintype "tri_state"))
      (node (ref "R1") (pin "P$1") (pinfunction "1_P$1") (pintype "passive"))
    )
    (net (code "2") (name "AN2") (class "Default")
      (node (ref "IC1") (pin "1") (pinfunction "QB_1") (pintype "tri_state"))
      (node (ref "R2") (pin "P$1") (pinfunction "1_P$1") (pintype "passive"))
    )
    (net (code "3") (name "AN3") (class "Default")
      (node (ref "IC1") (pin "2") (pinfunction "QC_2") (pintype "tri_state"))
      (node (ref "R3") (pin "P$1") (pinfunction "1_P$1") (pintype "passive"))
    )
    (net (code "4") (name "AN4") (class "Default")
      (node (ref "IC1") (pin "3") (pinfunction "QD_3") (pintype "tri_state"))
      (node (ref "R4") (pin "P$1") (pinfunction "1_P$1") (pintype "passive"))
    )
    (net (code "5") (name "AN5") (class "Default")
      (node (ref "IC1") (pin "4") (pinfunction "QE_4") (pintype "tri_state"))
      (node (ref "R5") (pin "P$1") (pinfunction "1_P$1") (pintype "passive"))
    )
    (net (code "6") (name "AN6") (class "Default")
      (node (ref "IC1") (pin "5") (pinfunction "QF_5") (pintype "tri_state"))
      (node (ref "R6") (pin "P$1") (pinfunction "1_P$1") (pintype "passive"))
    )
    (net (code "7") (name "AN7") (class "Default")
      (node (ref "IC1") (pin "6") (pinfunction "QG_6") (pintype "tri_state"))
      (node (ref "R7") (pin "P$1") (pinfunction "1_P$1") (pintype "passive"))
    )
    (net (code "8") (name "AN8") (class "Default")
      (node (ref "IC1") (pin "7") (pinfunction "QH_7") (pintype "tri_state"))
      (node (ref "R8") (pin "P$1") (pinfunction "1_P$1") (pintype "passive"))
    )
    (net (code "9") (name "AN9") (class "Default")
      (node (ref "IC2") (pin "15") (pinfunction "QA_15") (pintype "tri_state"))
      (node (ref "R9") (pin "P$1") (pinfunction "1_P$1") (pintype "passive"))
    )
    (net (code "10") (name "AN10") (class "Default")
      (node (ref "IC2") (pin "1") (pinfunction "QB_1") (pintype "tri_state"))
      (node (ref "R10") (pin "P$1") (pinfunction "1_P$1") (pintype "passive"))
    )
    (net (code "11") (name "AN11") (class "Default")
      (node (ref "IC2") (pin "2") (pinfunction "QC_2") (pintype "tri_state"))
      (node (ref "R11") (pin "P$1") (pinfunction "1_P$1") (pintype "passive"))
    )
    (net (code "12") (name "AN12") (class "Default")
      (node (ref "IC2") (pin "3") (pinfunction "QD_3") (pintype "tri_state"))
      (node (ref "R12") (pin "P$1") (pinfunction "1_P$1") (pintype "passive"))
    )
    (net (code "13") (name "AN13") (class "Default")
      (node (ref "IC2") (pin "4") (pinfunction "QE_4") (pintype "tri_state"))
      (node (ref "R13") (pin "P$1") (pinfunction "1_P$1") (pintype "passive"))
    )
    (net (code "14") (name "AN14") (class "Default")
      (node (ref "IC2") (pin "5") (pinfunction "QF_5") (pintype "tri_state"))
      (node (ref "R14") (pin "P$1") (pinfunction "1_P$1") (pintype "passive"))
    )
    (net (code "15") (name "AN15") (class "Default")
      (node (ref "IC2") (pin "6") (pinfunction "QG_6") (pintype "tri_state"))
      (node (ref "R15") (pin "P$1") (pinfunction "1_P$1") (pintype "passive"))
    )
    (net (code "16") (name "AN16") (class "Default")
      (node (ref "IC2") (pin "7") (pinfunction "QH_7") (pintype "tri_state"))
      (node (ref "R16") (pin "P$1") (pinfunction "1_P$1") (pintype "passive"))
    )
    (net (code "17") (name "AN17") (class "Default")
      (node (ref "IC3") (pin "15") (pinfunction "QA_15") (pintype "tri_state"))
      (node (ref "R17") (pin "P$1") (pinfunction "1_P$1") (pintype "passive"))
    )
    (net (code "18") (name "AN18") (class "Default")
      (node (ref "IC3") (pin "1") (pinfunction "QB_1") (pintype "tri_state"))
      (node (ref "R18") (pin "P$1") (pinfunction "1_P$1") (pintype "passive"))
    )
    (net (code "19") (name "AN19") (class "Default")
      (node (ref "IC3") (pin "2") (pinfunction "QC_2") (pintype "tri_state"))
      (node (ref "R19") (pin "P$1") (pinfunction "1_P$1") (pintype "passive"))
    )
    (net (code "20") (name "AN20") (class "Default")
      (node (ref "IC3") (pin "3") (pinfunction "QD_3") (pintype "tri_state"))
      (node (ref "R20") (pin "P$1") (pinfunction "1_P$1") (pintype "passive"))
    )
    (net (code "21") (name "AN21") (class "Default")
      (node (ref "IC3") (pin "4") (pinfunction "QE_4") (pintype "tri_state"))
      (node (ref "R21") (pin "P$1") (pinfunction "1_P$1") (pintype "passive"))
    )
    (net (code "22") (name "AN22") (class "Default")
      (node (ref "IC3") (pin "5") (pinfunction "QF_5") (pintype "tri_state"))
      (node (ref "R22") (pin "P$1") (pinfunction "1_P$1") (pintype "passive"))
    )
    (net (code "23") (name "AN23") (class "Default")
      (node (ref "IC3") (pin "6") (pinfunction "QG_6") (pintype "tri_state"))
      (node (ref "R23") (pin "P$1") (pinfunction "1_P$1") (pintype "passive"))
    )
    (net (code "24") (name "AN24") (class "Default")
      (node (ref "IC3") (pin "7") (pinfunction "QH_7") (pintype "tri_state"))
      (node (ref "R24") (pin "P$1") (pinfunction "1_P$1") (pintype "passive"))
    )
    (net (code "25") (name "AN25") (class "Default")
      (node (ref "IC4") (pin "25") (pinfunction "PC2(ADC2)_25") (pintype "bidirectional"))
      (node (ref "R25") (pin "P$1") (pinfunction "1_P$1") (pintype "passive"))
      (node (ref "R28") (pin "P$1") (pinfunction "1_P$1") (pintype "passive"))
      (node (ref "R31") (pin "P$1") (pinfunction "1_P$1") (pintype "passive"))
      (node (ref "R34") (pin "P$1") (pinfunction "1_P$1") (pintype "passive"))
    )
    (net (code "26") (name "AN26") (class "Default")
      (node (ref "IC4") (pin "24") (pinfunction "PC1(ADC1)_24") (pintype "bidirectional"))
      (node (ref "R26") (pin "P$1") (pinfunction "1_P$1") (pintype "passive"))
      (node (ref "R29") (pin "P$1") (pinfunction "1_P$1") (pintype "passive"))
      (node (ref "R32") (pin "P$1") (pinfunction "1_P$1") (pintype "passive"))
      (node (ref "R35") (pin "P$1") (pinfunction "1_P$1") (pintype "passive"))
    )
    (net (code "27") (name "AN27") (class "Default")
      (node (ref "IC4") (pin "23") (pinfunction "PC0(ADC0)_23") (pintype "bidirectional"))
      (node (ref "R27") (pin "P$1") (pinfunction "1_P$1") (pintype "passive"))
      (node (ref "R30") (pin "P$1") (pinfunction "1_P$1") (pintype "passive"))
      (node (ref "R33") (pin "P$1") (pinfunction "1_P$1") (pintype "passive"))
      (node (ref "R36") (pin "P$1") (pinfunction "1_P$1") (pintype "passive"))
    )
    (net (code "28") (name "AVR-RX") (class "Default")
      (node (ref "CN1") (pin "4") (pinfunction "TXD_4") (pintype "bidirectional"))
      (node (ref "IC4") (pin "2") (pinfunction "PD0(RXD)_2") (pintype "bidirectional"))
    )
    (net (code "29") (name "AVR-TX") (class "Default")
      (node (ref "CN1") (pin "5") (pinfunction "RXD_5") (pintype "bidirectional"))
      (node (ref "IC4") (pin "3") (pinfunction "PD1(TXD)_3") (pintype "bidirectional"))
    )
    (net (code "30") (name "BUTTON1") (class "Default")
      (node (ref "IC4") (pin "14") (pinfunction "PB0(ICP)_14") (pintype "bidirectional"))
      (node (ref "U$17") (pin "2A") (pinfunction "2A_2A") (pintype "passive"))
    )
    (net (code "31") (name "BUTTON2") (class "Default")
      (node (ref "IC4") (pin "15") (pinfunction "PB1(OC1A)_15") (pintype "bidirectional"))
      (node (ref "U$18") (pin "2A") (pinfunction "2A_2A") (pintype "passive"))
    )
    (net (code "32") (name "CA1") (class "Default")
      (node (ref "IC4") (pin "4") (pinfunction "PD2(INT0)_4") (pintype "bidirectional"))
      (node (ref "Q1") (pin "2") (pinfunction "G_2") (pintype "passive"))
    )
    (net (code "33") (name "CA1-BUS") (class "Default")
      (node (ref "D1") (pin "A") (pinfunction "A_A") (pintype "passive"))
      (node (ref "D101") (pin "A") (pinfunction "A_A") (pintype "passive"))
      (node (ref "D106") (pin "A") (pinfunction "A_A") (pintype "passive"))
      (node (ref "D11") (pin "A") (pinfunction "A_A") (pintype "passive"))
      (node (ref "D111") (pin "A") (pinfunction "A_A") (pintype "passive"))
      (node (ref "D116") (pin "A") (pinfunction "A_A") (pintype "passive"))
      (node (ref "D121") (pin "A") (pinfunction "A_A") (pintype "passive"))
      (node (ref "D126") (pin "A") (pinfunction "A_A") (pintype "passive"))
      (node (ref "D131") (pin "A") (pinfunction "A_A") (pintype "passive"))
      (node (ref "D16") (pin "A") (pinfunction "A_A") (pintype "passive"))
      (node (ref "D21") (pin "A") (pinfunction "A_A") (pintype "passive"))
      (node (ref "D26") (pin "A") (pinfunction "A_A") (pintype "passive"))
      (node (ref "D31") (pin "A") (pinfunction "A_A") (pintype "passive"))
      (node (ref "D36") (pin "A") (pinfunction "A_A") (pintype "passive"))
      (node (ref "D41") (pin "A") (pinfunction "A_A") (pintype "passive"))
      (node (ref "D46") (pin "A") (pinfunction "A_A") (pintype "passive"))
      (node (ref "D51") (pin "A") (pinfunction "A_A") (pintype "passive"))
      (node (ref "D56") (pin "A") (pinfunction "A_A") (pintype "passive"))
      (node (ref "D6") (pin "A") (pinfunction "A_A") (pintype "passive"))
      (node (ref "D61") (pin "A") (pinfunction "A_A") (pintype "passive"))
      (node (ref "D66") (pin "A") (pinfunction "A_A") (pintype "passive"))
      (node (ref "D71") (pin "A") (pinfunction "A_A") (pintype "passive"))
      (node (ref "D76") (pin "A") (pinfunction "A_A") (pintype "passive"))
      (node (ref "D81") (pin "A") (pinfunction "A_A") (pintype "passive"))
      (node (ref "D86") (pin "A") (pinfunction "A_A") (pintype "passive"))
      (node (ref "D91") (pin "A") (pinfunction "A_A") (pintype "passive"))
      (node (ref "D96") (pin "A") (pinfunction "A_A") (pintype "passive"))
      (node (ref "Q1") (pin "3") (pinfunction "D_3") (pintype "passive"))
    )
    (net (code "34") (name "CA2") (class "Default")
      (node (ref "IC4") (pin "5") (pinfunction "PD3(INT1)_5") (pintype "bidirectional"))
      (node (ref "Q2") (pin "2") (pinfunction "G_2") (pintype "passive"))
    )
    (net (code "35") (name "CA2-BUS") (class "Default")
      (node (ref "D102") (pin "A") (pinfunction "A_A") (pintype "passive"))
      (node (ref "D107") (pin "A") (pinfunction "A_A") (pintype "passive"))
      (node (ref "D112") (pin "A") (pinfunction "A_A") (pintype "passive"))
      (node (ref "D117") (pin "A") (pinfunction "A_A") (pintype "passive"))
      (node (ref "D12") (pin "A") (pinfunction "A_A") (pintype "passive"))
      (node (ref "D122") (pin "A") (pinfunction "A_A") (pintype "passive"))
      (node (ref "D127") (pin "A") (pinfunction "A_A") (pintype "passive"))
      (node (ref "D132") (pin "A") (pinfunction "A_A") (pintype "passive"))
      (node (ref "D17") (pin "A") (pinfunction "A_A") (pintype "passive"))
      (node (ref "D2") (pin "A") (pinfunction "A_A") (pintype "passive"))
      (node (ref "D22") (pin "A") (pinfunction "A_A") (pintype "passive"))
      (node (ref "D27") (pin "A") (pinfunction "A_A") (pintype "passive"))
      (node (ref "D32") (pin "A") (pinfunction "A_A") (pintype "passive"))
      (node (ref "D37") (pin "A") (pinfunction "A_A") (pintype "passive"))
      (node (ref "D42") (pin "A") (pinfunction "A_A") (pintype "passive"))
      (node (ref "D47") (pin "A") (pinfunction "A_A") (pintype "passive"))
      (node (ref "D52") (pin "A") (pinfunction "A_A") (pintype "passive"))
      (node (ref "D57") (pin "A") (pinfunction "A_A") (pintype "passive"))
      (node (ref "D62") (pin "A") (pinfunction "A_A") (pintype "passive"))
      (node (ref "D67") (pin "A") (pinfunction "A_A") (pintype "passive"))
      (node (ref "D7") (pin "A") (pinfunction "A_A") (pintype "passive"))
      (node (ref "D72") (pin "A") (pinfunction "A_A") (pintype "passive"))
      (node (ref "D77") (pin "A") (pinfunction "A_A") (pintype "passive"))
      (node (ref "D82") (pin "A") (pinfunction "A_A") (pintype "passive"))
      (node (ref "D87") (pin "A") (pinfunction "A_A") (pintype "passive"))
      (node (ref "D92") (pin "A") (pinfunction "A_A") (pintype "passive"))
      (node (ref "D97") (pin "A") (pinfunction "A_A") (pintype "passive"))
      (node (ref "Q2") (pin "3") (pinfunction "D_3") (pintype "passive"))
    )
    (net (code "36") (name "CA3") (class "Default")
      (node (ref "IC4") (pin "6") (pinfunction "PD4(XCK/T0)_6") (pintype "bidirectional"))
      (node (ref "Q3") (pin "2") (pinfunction "G_2") (pintype "passive"))
    )
    (net (code "37") (name "CA3-BUS") (class "Default")
      (node (ref "D103") (pin "A") (pinfunction "A_A") (pintype "passive"))
      (node (ref "D108") (pin "A") (pinfunction "A_A") (pintype "passive"))
      (node (ref "D113") (pin "A") (pinfunction "A_A") (pintype "passive"))
      (node (ref "D118") (pin "A") (pinfunction "A_A") (pintype "passive"))
      (node (ref "D123") (pin "A") (pinfunction "A_A") (pintype "passive"))
      (node (ref "D128") (pin "A") (pinfunction "A_A") (pintype "passive"))
      (node (ref "D13") (pin "A") (pinfunction "A_A") (pintype "passive"))
      (node (ref "D18") (pin "A") (pinfunction "A_A") (pintype "passive"))
      (node (ref "D23") (pin "A") (pinfunction "A_A") (pintype "passive"))
      (node (ref "D28") (pin "A") (pinfunction "A_A") (pintype "passive"))
      (node (ref "D3") (pin "A") (pinfunction "A_A") (pintype "passive"))
      (node (ref "D33") (pin "A") (pinfunction "A_A") (pintype "passive"))
      (node (ref "D38") (pin "A") (pinfunction "A_A") (pintype "passive"))
      (node (ref "D43") (pin "A") (pinfunction "A_A") (pintype "passive"))
      (node (ref "D48") (pin "A") (pinfunction "A_A") (pintype "passive"))
      (node (ref "D53") (pin "A") (pinfunction "A_A") (pintype "passive"))
      (node (ref "D58") (pin "A") (pinfunction "A_A") (pintype "passive"))
      (node (ref "D63") (pin "A") (pinfunction "A_A") (pintype "passive"))
      (node (ref "D68") (pin "A") (pinfunction "A_A") (pintype "passive"))
      (node (ref "D73") (pin "A") (pinfunction "A_A") (pintype "passive"))
      (node (ref "D78") (pin "A") (pinfunction "A_A") (pintype "passive"))
      (node (ref "D8") (pin "A") (pinfunction "A_A") (pintype "passive"))
      (node (ref "D83") (pin "A") (pinfunction "A_A") (pintype "passive"))
      (node (ref "D88") (pin "A") (pinfunction "A_A") (pintype "passive"))
      (node (ref "D93") (pin "A") (pinfunction "A_A") (pintype "passive"))
      (node (ref "D98") (pin "A") (pinfunction "A_A") (pintype "passive"))
      (node (ref "Q3") (pin "3") (pinfunction "D_3") (pintype "passive"))
    )
    (net (code "38") (name "CA4") (class "Default")
      (node (ref "IC4") (pin "11") (pinfunction "PD5(T1)_11") (pintype "bidirectional"))
      (node (ref "Q4") (pin "2") (pinfunction "G_2") (pintype "passive"))
    )
    (net (code "39") (name "CA4-BUS") (class "Default")
      (node (ref "D104") (pin "A") (pinfunction "A_A") (pintype "passive"))
      (node (ref "D109") (pin "A") (pinfunction "A_A") (pintype "passive"))
      (node (ref "D114") (pin "A") (pinfunction "A_A") (pintype "passive"))
      (node (ref "D119") (pin "A") (pinfunction "A_A") (pintype "passive"))
      (node (ref "D124") (pin "A") (pinfunction "A_A") (pintype "passive"))
      (node (ref "D129") (pin "A") (pinfunction "A_A") (pintype "passive"))
      (node (ref "D14") (pin "A") (pinfunction "A_A") (pintype "passive"))
      (node (ref "D19") (pin "A") (pinfunction "A_A") (pintype "passive"))
      (node (ref "D24") (pin "A") (pinfunction "A_A") (pintype "passive"))
      (node (ref "D29") (pin "A") (pinfunction "A_A") (pintype "passive"))
      (node (ref "D34") (pin "A") (pinfunction "A_A") (pintype "passive"))
      (node (ref "D39") (pin "A") (pinfunction "A_A") (pintype "passive"))
      (node (ref "D4") (pin "A") (pinfunction "A_A") (pintype "passive"))
      (node (ref "D44") (pin "A") (pinfunction "A_A") (pintype "passive"))
      (node (ref "D49") (pin "A") (pinfunction "A_A") (pintype "passive"))
      (node (ref "D54") (pin "A") (pinfunction "A_A") (pintype "passive"))
      (node (ref "D59") (pin "A") (pinfunction "A_A") (pintype "passive"))
      (node (ref "D64") (pin "A") (pinfunction "A_A") (pintype "passive"))
      (node (ref "D69") (pin "A") (pinfunction "A_A") (pintype "passive"))
      (node (ref "D74") (pin "A") (pinfunction "A_A") (pintype "passive"))
      (node (ref "D79") (pin "A") (pinfunction "A_A") (pintype "passive"))
      (node (ref "D84") (pin "A") (pinfunction "A_A") (pintype "passive"))
      (node (ref "D89") (pin "A") (pinfunction "A_A") (pintype "passive"))
      (node (ref "D9") (pin "A") (pinfunction "A_A") (pintype "passive"))
      (node (ref "D94") (pin "A") (pinfunction "A_A") (pintype "passive"))
      (node (ref "D99") (pin "A") (pinfunction "A_A") (pintype "passive"))
      (node (ref "Q4") (pin "3") (pinfunction "D_3") (pintype "passive"))
    )
    (net (code "40") (name "CA5") (class "Default")
      (node (ref "IC4") (pin "12") (pinfunction "PD6(AIN0)_12") (pintype "bidirectional"))
      (node (ref "Q5") (pin "2") (pinfunction "G_2") (pintype "passive"))
    )
    (net (code "41") (name "CA5-BUS") (class "Default")
      (node (ref "D10") (pin "A") (pinfunction "A_A") (pintype "passive"))
      (node (ref "D100") (pin "A") (pinfunction "A_A") (pintype "passive"))
      (node (ref "D105") (pin "A") (pinfunction "A_A") (pintype "passive"))
      (node (ref "D110") (pin "A") (pinfunction "A_A") (pintype "passive"))
      (node (ref "D115") (pin "A") (pinfunction "A_A") (pintype "passive"))
      (node (ref "D120") (pin "A") (pinfunction "A_A") (pintype "passive"))
      (node (ref "D125") (pin "A") (pinfunction "A_A") (pintype "passive"))
      (node (ref "D130") (pin "A") (pinfunction "A_A") (pintype "passive"))
      (node (ref "D15") (pin "A") (pinfunction "A_A") (pintype "passive"))
      (node (ref "D20") (pin "A") (pinfunction "A_A") (pintype "passive"))
      (node (ref "D25") (pin "A") (pinfunction "A_A") (pintype "passive"))
      (node (ref "D30") (pin "A") (pinfunction "A_A") (pintype "passive"))
      (node (ref "D35") (pin "A") (pinfunction "A_A") (pintype "passive"))
      (node (ref "D40") (pin "A") (pinfunction "A_A") (pintype "passive"))
      (node (ref "D45") (pin "A") (pinfunction "A_A") (pintype "passive"))
      (node (ref "D5") (pin "A") (pinfunction "A_A") (pintype "passive"))
      (node (ref "D50") (pin "A") (pinfunction "A_A") (pintype "passive"))
      (node (ref "D55") (pin "A") (pinfunction "A_A") (pintype "passive"))
      (node (ref "D60") (pin "A") (pinfunction "A_A") (pintype "passive"))
      (node (ref "D65") (pin "A") (pinfunction "A_A") (pintype "passive"))
      (node (ref "D70") (pin "A") (pinfunction "A_A") (pintype "passive"))
      (node (ref "D75") (pin "A") (pinfunction "A_A") (pintype "passive"))
      (node (ref "D80") (pin "A") (pinfunction "A_A") (pintype "passive"))
      (node (ref "D85") (pin "A") (pinfunction "A_A") (pintype "passive"))
      (node (ref "D90") (pin "A") (pinfunction "A_A") (pintype "passive"))
      (node (ref "D95") (pin "A") (pinfunction "A_A") (pintype "passive"))
      (node (ref "Q5") (pin "3") (pinfunction "D_3") (pintype "passive"))
    )
    (net (code "42") (name "GND") (class "Default")
      (node (ref "C1") (pin "2") (pinfunction "2_2") (pintype "passive"))
      (node (ref "C10") (pin "2") (pinfunction "2_2") (pintype "passive"))
      (node (ref "C11") (pin "2") (pinfunction "2_2") (pintype "passive"))
      (node (ref "C2") (pin "2") (pinfunction "2_2") (pintype "passive"))
      (node (ref "C3") (pin "2") (pinfunction "2_2") (pintype "passive"))
      (node (ref "C4") (pin "2") (pinfunction "2_2") (pintype "passive"))
      (node (ref "C5") (pin "C") (pinfunction "C_C") (pintype "bidirectional"))
      (node (ref "C7") (pin "2") (pinfunction "2_2") (pintype "passive"))
      (node (ref "C8") (pin "2") (pinfunction "2_2") (pintype "passive"))
      (node (ref "C9") (pin "2") (pinfunction "2_2") (pintype "passive"))
      (node (ref "CN1") (pin "1") (pinfunction "GND_1") (pintype "bidirectional"))
      (node (ref "IC1") (pin "13") (pinfunction "G_13") (pintype "input"))
      (node (ref "IC2") (pin "13") (pinfunction "G_13") (pintype "input"))
      (node (ref "IC3") (pin "13") (pinfunction "G_13") (pintype "input"))
      (node (ref "IC4") (pin "22") (pinfunction "GND_22") (pintype "power_in"))
      (node (ref "IC4") (pin "8") (pinfunction "GND_8") (pintype "power_in"))
      (node (ref "IC5") (pin "4") (pinfunction "GND_4") (pintype "bidirectional"))
      (node (ref "J1") (pin "GND") (pinfunction "GND_GND") (pintype "power_in"))
      (node (ref "J2") (pin "6") (pinfunction "GND_6") (pintype "passive"))
      (node (ref "Q1") (pin "1") (pinfunction "S_1") (pintype "passive"))
      (node (ref "Q2") (pin "1") (pinfunction "S_1") (pintype "passive"))
      (node (ref "Q3") (pin "1") (pinfunction "S_1") (pintype "passive"))
      (node (ref "Q4") (pin "1") (pinfunction "S_1") (pintype "passive"))
      (node (ref "Q5") (pin "1") (pinfunction "S_1") (pintype "passive"))
      (node (ref "U$17") (pin "1A") (pinfunction "1A_1A") (pintype "passive"))
      (node (ref "U$17") (pin "1B") (pinfunction "1B_1B") (pintype "passive"))
      (node (ref "U$18") (pin "1A") (pinfunction "1A_1A") (pintype "passive"))
      (node (ref "U$18") (pin "1B") (pinfunction "1B_1B") (pintype "passive"))
    )
    (net (code "43") (name "LATCH") (class "Default")
      (node (ref "IC1") (pin "12") (pinfunction "RCK_12") (pintype "input"))
      (node (ref "IC2") (pin "12") (pinfunction "RCK_12") (pintype "input"))
      (node (ref "IC3") (pin "12") (pinfunction "RCK_12") (pintype "input"))
      (node (ref "IC4") (pin "16") (pinfunction "PB2(SS/OC1B)_16") (pintype "bidirectional"))
    )
    (net (code "44") (name "MISO") (class "Default")
      (node (ref "IC4") (pin "18") (pinfunction "PB4(MISO)_18") (pintype "bidirectional"))
      (node (ref "J2") (pin "1") (pinfunction "MISO_1") (pintype "passive"))
    )
    (net (code "45") (name "MOSI") (class "Default")
      (node (ref "IC1") (pin "14") (pinfunction "SER_14") (pintype "input"))
      (node (ref "IC4") (pin "17") (pinfunction "PB3(MOSI/OC2)_17") (pintype "bidirectional"))
      (node (ref "J2") (pin "4") (pinfunction "MOSI_4") (pintype "passive"))
    )
    (net (code "46") (name "Net-(CN1-RTS)") (class "Default")
      (node (ref "C12") (pin "2") (pinfunction "2_2") (pintype "passive"))
      (node (ref "CN1") (pin "6") (pinfunction "RTS_6") (pintype "bidirectional"))
    )
    (net (code "47") (name "Net-(IC1A-QH*)") (class "Default")
      (node (ref "IC1") (pin "9") (pinfunction "QH*_9") (pintype "tri_state"))
      (node (ref "IC2") (pin "14") (pinfunction "SER_14") (pintype "input"))
    )
    (net (code "48") (name "Net-(IC2A-QH*)") (class "Default")
      (node (ref "IC2") (pin "9") (pinfunction "QH*_9") (pintype "tri_state"))
      (node (ref "IC3") (pin "14") (pinfunction "SER_14") (pintype "input"))
    )
    (net (code "49") (name "Net-(IC4-PB6(XTAL1{slash}TOSC1))") (class "Default")
      (node (ref "C2") (pin "1") (pinfunction "1_1") (pintype "passive"))
      (node (ref "IC4") (pin "9") (pinfunction "PB6(XTAL1/TOSC1)_9") (pintype "bidirectional"))
      (node (ref "X1") (pin "2") (pinfunction "2_2") (pintype "passive"))
    )
    (net (code "50") (name "Net-(IC4-PB7(XTAL2{slash}TOSC2))") (class "Default")
      (node (ref "C1") (pin "1") (pinfunction "1_1") (pintype "passive"))
      (node (ref "IC4") (pin "10") (pinfunction "PB7(XTAL2/TOSC2)_10") (pintype "bidirectional"))
      (node (ref "X1") (pin "1") (pinfunction "1_1") (pintype "passive"))
    )
    (net (code "51") (name "Net-(IC5-VBAT)") (class "Default")
      (node (ref "C5") (pin "A") (pinfunction "A_A") (pintype "bidirectional"))
      (node (ref "IC5") (pin "3") (pinfunction "VBAT_3") (pintype "bidirectional"))
    )
    (net (code "52") (name "Net-(IC5-XTAL1)") (class "Default")
      (node (ref "C4") (pin "1") (pinfunction "1_1") (pintype "passive"))
      (node (ref "IC5") (pin "1") (pinfunction "XTAL1_1") (pintype "bidirectional"))
      (node (ref "X2") (pin "2") (pinfunction "2_2") (pintype "passive"))
    )
    (net (code "53") (name "Net-(IC5-XTAL2)") (class "Default")
      (node (ref "C3") (pin "1") (pinfunction "1_1") (pintype "passive"))
      (node (ref "IC5") (pin "2") (pinfunction "XTAL2_2") (pintype "bidirectional"))
      (node (ref "X2") (pin "1") (pinfunction "1_1") (pintype "passive"))
    )
    (net (code "54") (name "Net-(R1-2)") (class "Default")
      (node (ref "D1") (pin "C") (pinfunction "C_C") (pintype "passive"))
      (node (ref "D2") (pin "C") (pinfunction "C_C") (pintype "passive"))
      (node (ref "D3") (pin "C") (pinfunction "C_C") (pintype "passive"))
      (node (ref "D4") (pin "C") (pinfunction "C_C") (pintype "passive"))
      (node (ref "D5") (pin "C") (pinfunction "C_C") (pintype "passive"))
      (node (ref "R1") (pin "P$2") (pinfunction "2_P$2") (pintype "passive"))
    )
    (net (code "55") (name "Net-(R2-2)") (class "Default")
      (node (ref "D10") (pin "C") (pinfunction "C_C") (pintype "passive"))
      (node (ref "D6") (pin "C") (pinfunction "C_C") (pintype "passive"))
      (node (ref "D7") (pin "C") (pinfunction "C_C") (pintype "passive"))
      (node (ref "D8") (pin "C") (pinfunction "C_C") (pintype "passive"))
      (node (ref "D9") (pin "C") (pinfunction "C_C") (pintype "passive"))
      (node (ref "R2") (pin "P$2") (pinfunction "2_P$2") (pintype "passive"))
    )
    (net (code "56") (name "Net-(R3-2)") (class "Default")
      (node (ref "D11") (pin "C") (pinfunction "C_C") (pintype "passive"))
      (node (ref "D12") (pin "C") (pinfunction "C_C") (pintype "passive"))
      (node (ref "D13") (pin "C") (pinfunction "C_C") (pintype "passive"))
      (node (ref "D14") (pin "C") (pinfunction "C_C") (pintype "passive"))
      (node (ref "D15") (pin "C") (pinfunction "C_C") (pintype "passive"))
      (node (ref "R3") (pin "P$2") (pinfunction "2_P$2") (pintype "passive"))
    )
    (net (code "57") (name "Net-(R4-2)") (class "Default")
      (node (ref "D16") (pin "C") (pinfunction "C_C") (pintype "passive"))
      (node (ref "D17") (pin "C") (pinfunction "C_C") (pintype "passive"))
      (node (ref "D18") (pin "C") (pinfunction "C_C") (pintype "passive"))
      (node (ref "D19") (pin "C") (pinfunction "C_C") (pintype "passive"))
      (node (ref "D20") (pin "C") (pinfunction "C_C") (pintype "passive"))
      (node (ref "R4") (pin "P$2") (pinfunction "2_P$2") (pintype "passive"))
    )
    (net (code "58") (name "Net-(R5-2)") (class "Default")
      (node (ref "D21") (pin "C") (pinfunction "C_C") (pintype "passive"))
      (node (ref "D22") (pin "C") (pinfunction "C_C") (pintype "passive"))
      (node (ref "D23") (pin "C") (pinfunction "C_C") (pintype "passive"))
      (node (ref "D24") (pin "C") (pinfunction "C_C") (pintype "passive"))
      (node (ref "D25") (pin "C") (pinfunction "C_C") (pintype "passive"))
      (node (ref "R5") (pin "P$2") (pinfunction "2_P$2") (pintype "passive"))
    )
    (net (code "59") (name "Net-(R6-2)") (class "Default")
      (node (ref "D26") (pin "C") (pinfunction "C_C") (pintype "passive"))
      (node (ref "D27") (pin "C") (pinfunction "C_C") (pintype "passive"))
      (node (ref "D28") (pin "C") (pinfunction "C_C") (pintype "passive"))
      (node (ref "D29") (pin "C") (pinfunction "C_C") (pintype "passive"))
      (node (ref "D30") (pin "C") (pinfunction "C_C") (pintype "passive"))
      (node (ref "R6") (pin "P$2") (pinfunction "2_P$2") (pintype "passive"))
    )
    (net (code "60") (name "Net-(R7-2)") (class "Default")
      (node (ref "D31") (pin "C") (pinfunction "C_C") (pintype "passive"))
      (node (ref "D32") (pin "C") (pinfunction "C_C") (pintype "passive"))
      (node (ref "D33") (pin "C") (pinfunction "C_C") (pintype "passive"))
      (node (ref "D34") (pin "C") (pinfunction "C_C") (pintype "passive"))
      (node (ref "D35") (pin "C") (pinfunction "C_C") (pintype "passive"))
      (node (ref "R7") (pin "P$2") (pinfunction "2_P$2") (pintype "passive"))
    )
    (net (code "61") (name "Net-(R8-2)") (class "Default")
      (node (ref "D36") (pin "C") (pinfunction "C_C") (pintype "passive"))
      (node (ref "D37") (pin "C") (pinfunction "C_C") (pintype "passive"))
      (node (ref "D38") (pin "C") (pinfunction "C_C") (pintype "passive"))
      (node (ref "D39") (pin "C") (pinfunction "C_C") (pintype "passive"))
      (node (ref "D40") (pin "C") (pinfunction "C_C") (pintype "passive"))
      (node (ref "R8") (pin "P$2") (pinfunction "2_P$2") (pintype "passive"))
    )
    (net (code "62") (name "Net-(R9-2)") (class "Default")
      (node (ref "D41") (pin "C") (pinfunction "C_C") (pintype "passive"))
      (node (ref "D42") (pin "C") (pinfunction "C_C") (pintype "passive"))
      (node (ref "D43") (pin "C") (pinfunction "C_C") (pintype "passive"))
      (node (ref "D44") (pin "C") (pinfunction "C_C") (pintype "passive"))
      (node (ref "D45") (pin "C") (pinfunction "C_C") (pintype "passive"))
      (node (ref "R9") (pin "P$2") (pinfunction "2_P$2") (pintype "passive"))
    )
    (net (code "63") (name "Net-(R10-2)") (class "Default")
      (node (ref "D46") (pin "C") (pinfunction "C_C") (pintype "passive"))
      (node (ref "D47") (pin "C") (pinfunction "C_C") (pintype "passive"))
      (node (ref "D48") (pin "C") (pinfunction "C_C") (pintype "passive"))
      (node (ref "D49") (pin "C") (pinfunction "C_C") (pintype "passive"))
      (node (ref "D50") (pin "C") (pinfunction "C_C") (pintype "passive"))
      (node (ref "R10") (pin "P$2") (pinfunction "2_P$2") (pintype "passive"))
    )
    (net (code "64") (name "Net-(R11-2)") (class "Default")
      (node (ref "D51") (pin "C") (pinfunction "C_C") (pintype "passive"))
      (node (ref "D52") (pin "C") (pinfunction "C_C") (pintype "passive"))
      (node (ref "D53") (pin "C") (pinfunction "C_C") (pintype "passive"))
      (node (ref "D54") (pin "C") (pinfunction "C_C") (pintype "passive"))
      (node (ref "D55") (pin "C") (pinfunction "C_C") (pintype "passive"))
      (node (ref "R11") (pin "P$2") (pinfunction "2_P$2") (pintype "passive"))
    )
    (net (code "65") (name "Net-(R12-2)") (class "Default")
      (node (ref "D56") (pin "C") (pinfunction "C_C") (pintype "passive"))
      (node (ref "D57") (pin "C") (pinfunction "C_C") (pintype "passive"))
      (node (ref "D58") (pin "C") (pinfunction "C_C") (pintype "passive"))
      (node (ref "D59") (pin "C") (pinfunction "C_C") (pintype "passive"))
      (node (ref "D60") (pin "C") (pinfunction "C_C") (pintype "passive"))
      (node (ref "R12") (pin "P$2") (pinfunction "2_P$2") (pintype "passive"))
    )
    (net (code "66") (name "Net-(R13-2)") (class "Default")
      (node (ref "D61") (pin "C") (pinfunction "C_C") (pintype "passive"))
      (node (ref "D62") (pin "C") (pinfunction "C_C") (pintype "passive"))
      (node (ref "D63") (pin "C") (pinfunction "C_C") (pintype "passive"))
      (node (ref "D64") (pin "C") (pinfunction "C_C") (pintype "passive"))
      (node (ref "D65") (pin "C") (pinfunction "C_C") (pintype "passive"))
      (node (ref "R13") (pin "P$2") (pinfunction "2_P$2") (pintype "passive"))
    )
    (net (code "67") (name "Net-(R14-2)") (class "Default")
      (node (ref "D66") (pin "C") (pinfunction "C_C") (pintype "passive"))
      (node (ref "D67") (pin "C") (pinfunction "C_C") (pintype "passive"))
      (node (ref "D68") (pin "C") (pinfunction "C_C") (pintype "passive"))
      (node (ref "D69") (pin "C") (pinfunction "C_C") (pintype "passive"))
      (node (ref "D70") (pin "C") (pinfunction "C_C") (pintype "passive"))
      (node (ref "R14") (pin "P$2") (pinfunction "2_P$2") (pintype "passive"))
    )
    (net (code "68") (name "Net-(R15-2)") (class "Default")
      (node (ref "D71") (pin "C") (pinfunction "C_C") (pintype "passive"))
      (node (ref "D72") (pin "C") (pinfunction "C_C") (pintype "passive"))
      (node (ref "D73") (pin "C") (pinfunction "C_C") (pintype "passive"))
      (node (ref "D74") (pin "C") (pinfunction "C_C") (pintype "passive"))
      (node (ref "D75") (pin "C") (pinfunction "C_C") (pintype "passive"))
      (node (ref "R15") (pin "P$2") (pinfunction "2_P$2") (pintype "passive"))
    )
    (net (code "69") (name "Net-(R16-2)") (class "Default")
      (node (ref "D76") (pin "C") (pinfunction "C_C") (pintype "passive"))
      (node (ref "D77") (pin "C") (pinfunction "C_C") (pintype "passive"))
      (node (ref "D78") (pin "C") (pinfunction "C_C") (pintype "passive"))
      (node (ref "D79") (pin "C") (pinfunction "C_C") (pintype "passive"))
      (node (ref "D80") (pin "C") (pinfunction "C_C") (pintype "passive"))
      (node (ref "R16") (pin "P$2") (pinfunction "2_P$2") (pintype "passive"))
    )
    (net (code "70") (name "Net-(R17-2)") (class "Default")
      (node (ref "D81") (pin "C") (pinfunction "C_C") (pintype "passive"))
      (node (ref "D82") (pin "C") (pinfunction "C_C") (pintype "passive"))
      (node (ref "D83") (pin "C") (pinfunction "C_C") (pintype "passive"))
      (node (ref "D84") (pin "C") (pinfunction "C_C") (pintype "passive"))
      (node (ref "D85") (pin "C") (pinfunction "C_C") (pintype "passive"))
      (node (ref "R17") (pin "P$2") (pinfunction "2_P$2") (pintype "passive"))
    )
    (net (code "71") (name "Net-(R18-2)") (class "Default")
      (node (ref "D86") (pin "C") (pinfunction "C_C") (pintype "passive"))
      (node (ref "D87") (pin "C") (pinfunction "C_C") (pintype "passive"))
      (node (ref "D88") (pin "C") (pinfunction "C_C") (pintype "passive"))
      (node (ref "D89") (pin "C") (pinfunction "C_C") (pintype "passive"))
      (node (ref "D90") (pin "C") (pinfunction "C_C") (pintype "passive"))
      (node (ref "R18") (pin "P$2") (pinfunction "2_P$2") (pintype "passive"))
    )
    (net (code "72") (name "Net-(R19-2)") (class "Default")
      (node (ref "D91") (pin "C") (pinfunction "C_C") (pintype "passive"))
      (node (ref "D92") (pin "C") (pinfunction "C_C") (pintype "passive"))
      (node (ref "D93") (pin "C") (pinfunction "C_C") (pintype "passive"))
      (node (ref "D94") (pin "C") (pinfunction "C_C") (pintype "passive"))
      (node (ref "D95") (pin "C") (pinfunction "C_C") (pintype "passive"))
      (node (ref "R19") (pin "P$2") (pinfunction "2_P$2") (pintype "passive"))
    )
    (net (code "73") (name "Net-(R20-2)") (class "Default")
      (node (ref "D100") (pin "C") (pinfunction "C_C") (pintype "passive"))
      (node (ref "D96") (pin "C") (pinfunction "C_C") (pintype "passive"))
      (node (ref "D97") (pin "C") (pinfunction "C_C") (pintype "passive"))
      (node (ref "D98") (pin "C") (pinfunction "C_C") (pintype "passive"))
      (node (ref "D99") (pin "C") (pinfunction "C_C") (pintype "passive"))
      (node (ref "R20") (pin "P$2") (pinfunction "2_P$2") (pintype "passive"))
    )
    (net (code "74") (name "Net-(R21-2)") (class "Default")
      (node (ref "D101") (pin "C") (pinfunction "C_C") (pintype "passive"))
      (node (ref "D102") (pin "C") (pinfunction "C_C") (pintype "passive"))
      (node (ref "D103") (pin "C") (pinfunction "C_C") (pintype "passive"))
      (node (ref "D104") (pin "C") (pinfunction "C_C") (pintype "passive"))
      (node (ref "D105") (pin "C") (pinfunction "C_C") (pintype "passive"))
      (node (ref "R21") (pin "P$2") (pinfunction "2_P$2") (pintype "passive"))
    )
    (net (code "75") (name "Net-(R22-2)") (class "Default")
      (node (ref "D106") (pin "C") (pinfunction "C_C") (pintype "passive"))
      (node (ref "D107") (pin "C") (pinfunction "C_C") (pintype "passive"))
      (node (ref "D108") (pin "C") (pinfunction "C_C") (pintype "passive"))
      (node (ref "D109") (pin "C") (pinfunction "C_C") (pintype "passive"))
      (node (ref "D110") (pin "C") (pinfunction "C_C") (pintype "passive"))
      (node (ref "R22") (pin "P$2") (pinfunction "2_P$2") (pintype "passive"))
    )
    (net (code "76") (name "Net-(R23-2)") (class "Default")
      (node (ref "D111") (pin "C") (pinfunction "C_C") (pintype "passive"))
      (node (ref "D112") (pin "C") (pinfunction "C_C") (pintype "passive"))
      (node (ref "D113") (pin "C") (pinfunction "C_C") (pintype "passive"))
      (node (ref "D114") (pin "C") (pinfunction "C_C") (pintype "passive"))
      (node (ref "D115") (pin "C") (pinfunction "C_C") (pintype "passive"))
      (node (ref "R23") (pin "P$2") (pinfunction "2_P$2") (pintype "passive"))
    )
    (net (code "77") (name "Net-(R24-2)") (class "Default")
      (node (ref "D116") (pin "C") (pinfunction "C_C") (pintype "passive"))
      (node (ref "D117") (pin "C") (pinfunction "C_C") (pintype "passive"))
      (node (ref "D118") (pin "C") (pinfunction "C_C") (pintype "passive"))
      (node (ref "D119") (pin "C") (pinfunction "C_C") (pintype "passive"))
      (node (ref "D120") (pin "C") (pinfunction "C_C") (pintype "passive"))
      (node (ref "R24") (pin "P$2") (pinfunction "2_P$2") (pintype "passive"))
    )
    (net (code "78") (name "Net-(R25-2)") (class "Default")
      (node (ref "D121") (pin "C") (pinfunction "C_C") (pintype "passive"))
      (node (ref "R25") (pin "P$2") (pinfunction "2_P$2") (pintype "passive"))
    )
    (net (code "79") (name "Net-(R26-2)") (class "Default")
      (node (ref "D122") (pin "C") (pinfunction "C_C") (pintype "passive"))
      (node (ref "R26") (pin "P$2") (pinfunction "2_P$2") (pintype "passive"))
    )
    (net (code "80") (name "Net-(R27-2)") (class "Default")
      (node (ref "D123") (pin "C") (pinfunction "C_C") (pintype "passive"))
      (node (ref "R27") (pin "P$2") (pinfunction "2_P$2") (pintype "passive"))
    )
    (net (code "81") (name "Net-(R28-2)") (class "Default")
      (node (ref "D124") (pin "C") (pinfunction "C_C") (pintype "passive"))
      (node (ref "R28") (pin "P$2") (pinfunction "2_P$2") (pintype "passive"))
    )
    (net (code "82") (name "Net-(R29-2)") (class "Default")
      (node (ref "D125") (pin "C") (pinfunction "C_C") (pintype "passive"))
      (node (ref "R29") (pin "P$2") (pinfunction "2_P$2") (pintype "passive"))
    )
    (net (code "83") (name "Net-(R30-2)") (class "Default")
      (node (ref "D126") (pin "C") (pinfunction "C_C") (pintype "passive"))
      (node (ref "R30") (pin "P$2") (pinfunction "2_P$2") (pintype "passive"))
    )
    (net (code "84") (name "Net-(R31-2)") (class "Default")
      (node (ref "D127") (pin "C") (pinfunction "C_C") (pintype "passive"))
      (node (ref "R31") (pin "P$2") (pinfunction "2_P$2") (pintype "passive"))
    )
    (net (code "85") (name "Net-(R32-2)") (class "Default")
      (node (ref "D128") (pin "C") (pinfunction "C_C") (pintype "passive"))
      (node (ref "R32") (pin "P$2") (pinfunction "2_P$2") (pintype "passive"))
    )
    (net (code "86") (name "Net-(R33-2)") (class "Default")
      (node (ref "D129") (pin "C") (pinfunction "C_C") (pintype "passive"))
      (node (ref "R33") (pin "P$2") (pinfunction "2_P$2") (pintype "passive"))
    )
    (net (code "87") (name "Net-(R34-2)") (class "Default")
      (node (ref "D130") (pin "C") (pinfunction "C_C") (pintype "passive"))
      (node (ref "R34") (pin "P$2") (pinfunction "2_P$2") (pintype "passive"))
    )
    (net (code "88") (name "Net-(R35-2)") (class "Default")
      (node (ref "D131") (pin "C") (pinfunction "C_C") (pintype "passive"))
      (node (ref "R35") (pin "P$2") (pinfunction "2_P$2") (pintype "passive"))
    )
    (net (code "89") (name "Net-(R36-2)") (class "Default")
      (node (ref "D132") (pin "C") (pinfunction "C_C") (pintype "passive"))
      (node (ref "R36") (pin "P$2") (pinfunction "2_P$2") (pintype "passive"))
    )
    (net (code "90") (name "RESET") (class "Default")
      (node (ref "C12") (pin "1") (pinfunction "1_1") (pintype "passive"))
      (node (ref "IC4") (pin "1") (pinfunction "PC6(/RESET)_1") (pintype "bidirectional"))
      (node (ref "J2") (pin "5") (pinfunction "RESET_5") (pintype "passive"))
      (node (ref "R37") (pin "P$2") (pinfunction "2_P$2") (pintype "passive"))
    )
    (net (code "91") (name "SCK") (class "Default")
      (node (ref "IC1") (pin "11") (pinfunction "SCK_11") (pintype "input"))
      (node (ref "IC2") (pin "11") (pinfunction "SCK_11") (pintype "input"))
      (node (ref "IC3") (pin "11") (pinfunction "SCK_11") (pintype "input"))
      (node (ref "IC4") (pin "19") (pinfunction "PB5(SCK)_19") (pintype "bidirectional"))
      (node (ref "J2") (pin "3") (pinfunction "SCK_3") (pintype "passive"))
    )
    (net (code "92") (name "SCL") (class "Default")
      (node (ref "IC4") (pin "28") (pinfunction "PC5(ADC5/SCL)_28") (pintype "bidirectional"))
      (node (ref "IC5") (pin "6") (pinfunction "SCL_6") (pintype "bidirectional"))
    )
    (net (code "93") (name "SDA") (class "Default")
      (node (ref "IC4") (pin "27") (pinfunction "PC4(ADC4/SDA)_27") (pintype "bidirectional"))
      (node (ref "IC5") (pin "5") (pinfunction "SDA_5") (pintype "bidirectional"))
    )
    (net (code "94") (name "VCC") (class "Default")
      (node (ref "C10") (pin "1") (pinfunction "1_1") (pintype "passive"))
      (node (ref "C11") (pin "1") (pinfunction "1_1") (pintype "passive"))
      (node (ref "C7") (pin "1") (pinfunction "1_1") (pintype "passive"))
      (node (ref "C8") (pin "1") (pinfunction "1_1") (pintype "passive"))
      (node (ref "C9") (pin "1") (pinfunction "1_1") (pintype "passive"))
      (node (ref "CN1") (pin "3") (pinfunction "VCC_3") (pintype "bidirectional"))
      (node (ref "IC1") (pin "10") (pinfunction "SCL_10") (pintype "input"))
      (node (ref "IC2") (pin "10") (pinfunction "SCL_10") (pintype "input"))
      (node (ref "IC3") (pin "10") (pinfunction "SCL_10") (pintype "input"))
      (node (ref "IC4") (pin "20") (pinfunction "AVCC_20") (pintype "power_in"))
      (node (ref "IC4") (pin "7") (pinfunction "VCC_7") (pintype "power_in"))
      (node (ref "IC5") (pin "8") (pinfunction "VCC_8") (pintype "bidirectional"))
      (node (ref "J1") (pin "VBUS") (pinfunction "VBUS_VBUS") (pintype "power_in"))
      (node (ref "J2") (pin "2") (pinfunction "V+_2") (pintype "passive"))
      (node (ref "R37") (pin "P$1") (pinfunction "1_P$1") (pintype "passive"))
    )
    (net (code "95") (name "unconnected-(CN1-CTS-Pad2)") (class "Default")
      (node (ref "CN1") (pin "2") (pinfunction "CTS_2") (pintype "bidirectional"))
    )
    (net (code "96") (name "unconnected-(IC3A-QH*-Pad9)") (class "Default")
      (node (ref "IC3") (pin "9") (pinfunction "QH*_9") (pintype "tri_state"))
    )
    (net (code "97") (name "unconnected-(IC4-AREF-Pad21)") (class "Default")
      (node (ref "IC4") (pin "21") (pinfunction "AREF_21") (pintype "passive"))
    )
    (net (code "98") (name "unconnected-(IC4-PC3(ADC3)-Pad26)") (class "Default")
      (node (ref "IC4") (pin "26") (pinfunction "PC3(ADC3)_26") (pintype "bidirectional"))
    )
    (net (code "99") (name "unconnected-(IC4-PD7(AIN1)-Pad13)") (class "Default")
      (node (ref "IC4") (pin "13") (pinfunction "PD7(AIN1)_13") (pintype "bidirectional"))
    )
    (net (code "100") (name "unconnected-(IC5-MFP-Pad7)") (class "Default")
      (node (ref "IC5") (pin "7") (pinfunction "MFP_7") (pintype "bidirectional"))
    )
    (net (code "101") (name "unconnected-(U$17-Pad2B)") (class "Default")
      (node (ref "U$17") (pin "2B") (pinfunction "2B_2B") (pintype "passive"))
    )
    (net (code "102") (name "unconnected-(U$18-Pad2B)") (class "Default")
      (node (ref "U$18") (pin "2B") (pinfunction "2B_2B") (pintype "passive"))
    )
  )
)
